# BloopPadMaxx_00.net
KiCad netlist of a schematic drawn in Altium Designer
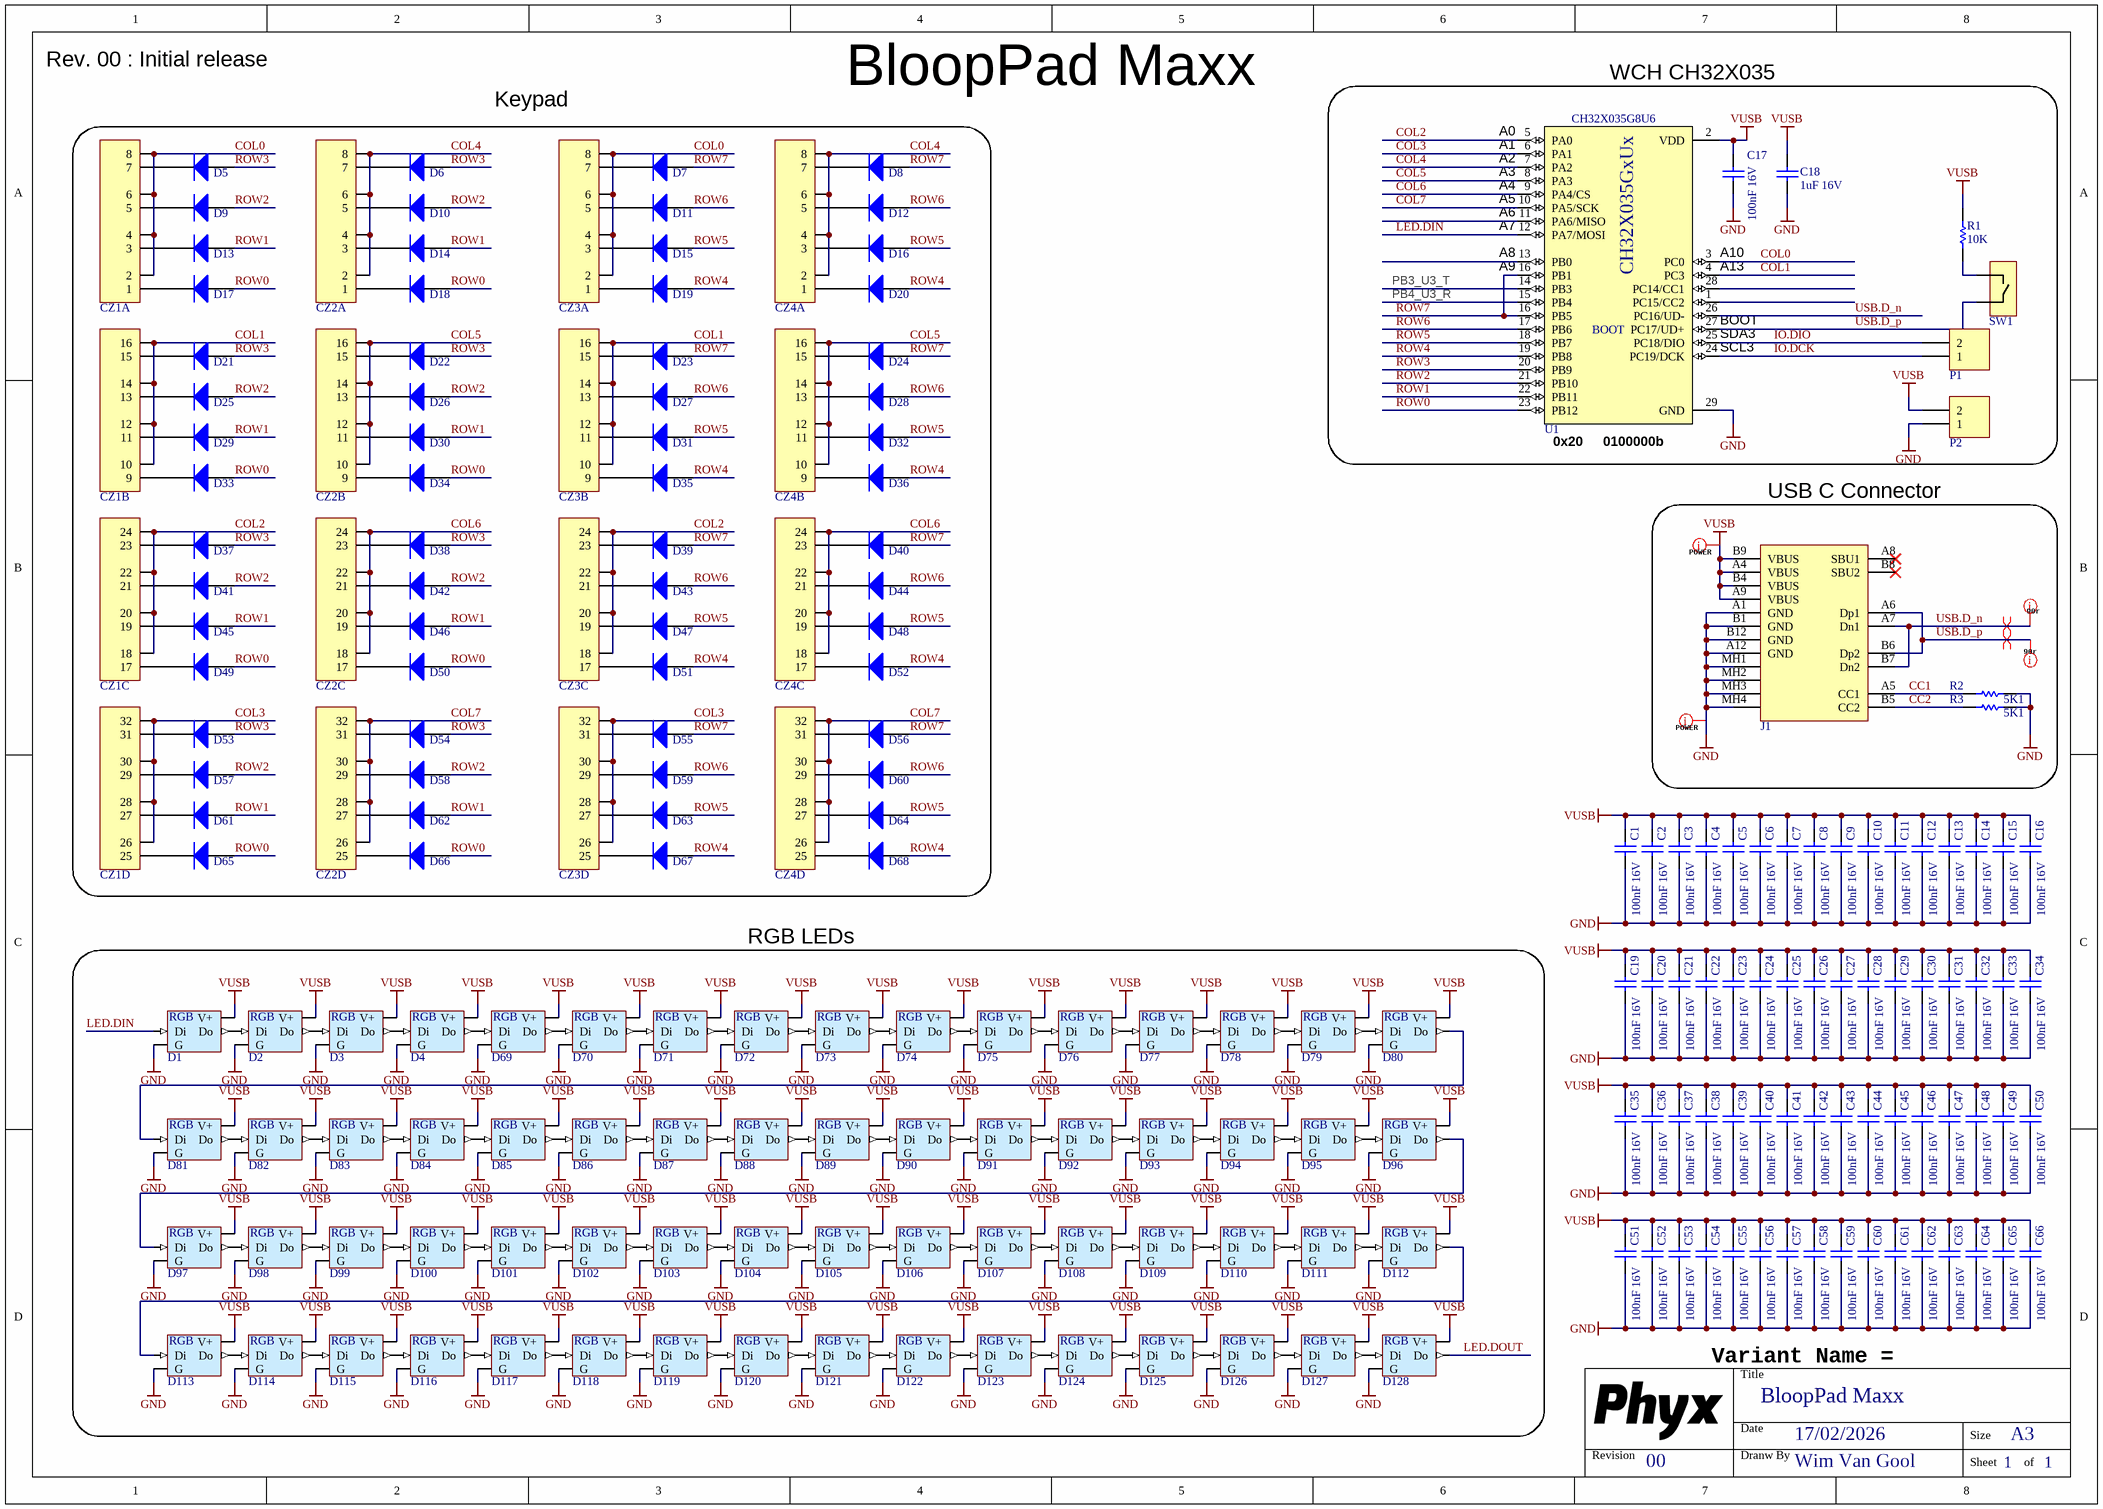
[diagram p0: BloopPadMaxx_00.SchDoc]

(export (version "E")
  (design (tool "Eeschema 10.0.6"))
  (components
    (comp (ref "C1")
      (value "100nF 16V")
      (footprint "C0603_N")
      (description "Capacitor Ceramic")
      (fields (field (name "Comment") "CAP_CERAMIC"))
      (libsource (lib "Phyx_Components") (part "CAP_CERAMIC"))
    )
    (comp (ref "C2")
      (value "100nF 16V")
      (footprint "C0603_N")
      (description "Capacitor Ceramic")
      (fields (field (name "Comment") "CAP_CERAMIC"))
      (libsource (lib "Phyx_Components") (part "CAP_CERAMIC"))
    )
    (comp (ref "C3")
      (value "100nF 16V")
      (footprint "C0603_N")
      (description "Capacitor Ceramic")
      (fields (field (name "Comment") "CAP_CERAMIC"))
      (libsource (lib "Phyx_Components") (part "CAP_CERAMIC"))
    )
    (comp (ref "C4")
      (value "100nF 16V")
      (footprint "C0603_N")
      (description "Capacitor Ceramic")
      (fields (field (name "Comment") "CAP_CERAMIC"))
      (libsource (lib "Phyx_Components") (part "CAP_CERAMIC"))
    )
    (comp (ref "C5")
      (value "100nF 16V")
      (footprint "C0603_N")
      (description "Capacitor Ceramic")
      (fields (field (name "Comment") "CAP_CERAMIC"))
      (libsource (lib "Phyx_Components") (part "CAP_CERAMIC"))
    )
    (comp (ref "C6")
      (value "100nF 16V")
      (footprint "C0603_N")
      (description "Capacitor Ceramic")
      (fields (field (name "Comment") "CAP_CERAMIC"))
      (libsource (lib "Phyx_Components") (part "CAP_CERAMIC"))
    )
    (comp (ref "C7")
      (value "100nF 16V")
      (footprint "C0603_N")
      (description "Capacitor Ceramic")
      (fields (field (name "Comment") "CAP_CERAMIC"))
      (libsource (lib "Phyx_Components") (part "CAP_CERAMIC"))
    )
    (comp (ref "C8")
      (value "100nF 16V")
      (footprint "C0603_N")
      (description "Capacitor Ceramic")
      (fields (field (name "Comment") "CAP_CERAMIC"))
      (libsource (lib "Phyx_Components") (part "CAP_CERAMIC"))
    )
    (comp (ref "C9")
      (value "100nF 16V")
      (footprint "C0603_N")
      (description "Capacitor Ceramic")
      (fields (field (name "Comment") "CAP_CERAMIC"))
      (libsource (lib "Phyx_Components") (part "CAP_CERAMIC"))
    )
    (comp (ref "C10")
      (value "100nF 16V")
      (footprint "C0603_N")
      (description "Capacitor Ceramic")
      (fields (field (name "Comment") "CAP_CERAMIC"))
      (libsource (lib "Phyx_Components") (part "CAP_CERAMIC"))
    )
    (comp (ref "C11")
      (value "100nF 16V")
      (footprint "C0603_N")
      (description "Capacitor Ceramic")
      (fields (field (name "Comment") "CAP_CERAMIC"))
      (libsource (lib "Phyx_Components") (part "CAP_CERAMIC"))
    )
    (comp (ref "C12")
      (value "100nF 16V")
      (footprint "C0603_N")
      (description "Capacitor Ceramic")
      (fields (field (name "Comment") "CAP_CERAMIC"))
      (libsource (lib "Phyx_Components") (part "CAP_CERAMIC"))
    )
    (comp (ref "C13")
      (value "100nF 16V")
      (footprint "C0603_N")
      (description "Capacitor Ceramic")
      (fields (field (name "Comment") "CAP_CERAMIC"))
      (libsource (lib "Phyx_Components") (part "CAP_CERAMIC"))
    )
    (comp (ref "C14")
      (value "100nF 16V")
      (footprint "C0603_N")
      (description "Capacitor Ceramic")
      (fields (field (name "Comment") "CAP_CERAMIC"))
      (libsource (lib "Phyx_Components") (part "CAP_CERAMIC"))
    )
    (comp (ref "C15")
      (value "100nF 16V")
      (footprint "C0603_N")
      (description "Capacitor Ceramic")
      (fields (field (name "Comment") "CAP_CERAMIC"))
      (libsource (lib "Phyx_Components") (part "CAP_CERAMIC"))
    )
    (comp (ref "C16")
      (value "100nF 16V")
      (footprint "C0603_N")
      (description "Capacitor Ceramic")
      (fields (field (name "Comment") "CAP_CERAMIC"))
      (libsource (lib "Phyx_Components") (part "CAP_CERAMIC"))
    )
    (comp (ref "C17")
      (value "100nF 16V")
      (footprint "C0603_N")
      (description "Capacitor Ceramic")
      (libsource (lib "Phyx_Components") (part "CAP_CERAMIC"))
    )
    (comp (ref "C18")
      (value "1uF 16V")
      (footprint "C0603_N")
      (description "Capacitor Ceramic")
      (libsource (lib "Phyx_Components") (part "CAP_CERAMIC"))
    )
    (comp (ref "C19")
      (value "100nF 16V")
      (footprint "C0603_N")
      (description "Capacitor Ceramic")
      (fields (field (name "Comment") "CAP_CERAMIC"))
      (libsource (lib "Phyx_Components") (part "CAP_CERAMIC"))
    )
    (comp (ref "C20")
      (value "100nF 16V")
      (footprint "C0603_N")
      (description "Capacitor Ceramic")
      (fields (field (name "Comment") "CAP_CERAMIC"))
      (libsource (lib "Phyx_Components") (part "CAP_CERAMIC"))
    )
    (comp (ref "C21")
      (value "100nF 16V")
      (footprint "C0603_N")
      (description "Capacitor Ceramic")
      (fields (field (name "Comment") "CAP_CERAMIC"))
      (libsource (lib "Phyx_Components") (part "CAP_CERAMIC"))
    )
    (comp (ref "C22")
      (value "100nF 16V")
      (footprint "C0603_N")
      (description "Capacitor Ceramic")
      (fields (field (name "Comment") "CAP_CERAMIC"))
      (libsource (lib "Phyx_Components") (part "CAP_CERAMIC"))
    )
    (comp (ref "C23")
      (value "100nF 16V")
      (footprint "C0603_N")
      (description "Capacitor Ceramic")
      (fields (field (name "Comment") "CAP_CERAMIC"))
      (libsource (lib "Phyx_Components") (part "CAP_CERAMIC"))
    )
    (comp (ref "C24")
      (value "100nF 16V")
      (footprint "C0603_N")
      (description "Capacitor Ceramic")
      (fields (field (name "Comment") "CAP_CERAMIC"))
      (libsource (lib "Phyx_Components") (part "CAP_CERAMIC"))
    )
    (comp (ref "C25")
      (value "100nF 16V")
      (footprint "C0603_N")
      (description "Capacitor Ceramic")
      (fields (field (name "Comment") "CAP_CERAMIC"))
      (libsource (lib "Phyx_Components") (part "CAP_CERAMIC"))
    )
    (comp (ref "C26")
      (value "100nF 16V")
      (footprint "C0603_N")
      (description "Capacitor Ceramic")
      (fields (field (name "Comment") "CAP_CERAMIC"))
      (libsource (lib "Phyx_Components") (part "CAP_CERAMIC"))
    )
    (comp (ref "C27")
      (value "100nF 16V")
      (footprint "C0603_N")
      (description "Capacitor Ceramic")
      (fields (field (name "Comment") "CAP_CERAMIC"))
      (libsource (lib "Phyx_Components") (part "CAP_CERAMIC"))
    )
    (comp (ref "C28")
      (value "100nF 16V")
      (footprint "C0603_N")
      (description "Capacitor Ceramic")
      (fields (field (name "Comment") "CAP_CERAMIC"))
      (libsource (lib "Phyx_Components") (part "CAP_CERAMIC"))
    )
    (comp (ref "C29")
      (value "100nF 16V")
      (footprint "C0603_N")
      (description "Capacitor Ceramic")
      (fields (field (name "Comment") "CAP_CERAMIC"))
      (libsource (lib "Phyx_Components") (part "CAP_CERAMIC"))
    )
    (comp (ref "C30")
      (value "100nF 16V")
      (footprint "C0603_N")
      (description "Capacitor Ceramic")
      (fields (field (name "Comment") "CAP_CERAMIC"))
      (libsource (lib "Phyx_Components") (part "CAP_CERAMIC"))
    )
    (comp (ref "C31")
      (value "100nF 16V")
      (footprint "C0603_N")
      (description "Capacitor Ceramic")
      (fields (field (name "Comment") "CAP_CERAMIC"))
      (libsource (lib "Phyx_Components") (part "CAP_CERAMIC"))
    )
    (comp (ref "C32")
      (value "100nF 16V")
      (footprint "C0603_N")
      (description "Capacitor Ceramic")
      (fields (field (name "Comment") "CAP_CERAMIC"))
      (libsource (lib "Phyx_Components") (part "CAP_CERAMIC"))
    )
    (comp (ref "C33")
      (value "100nF 16V")
      (footprint "C0603_N")
      (description "Capacitor Ceramic")
      (fields (field (name "Comment") "CAP_CERAMIC"))
      (libsource (lib "Phyx_Components") (part "CAP_CERAMIC"))
    )
    (comp (ref "C34")
      (value "100nF 16V")
      (footprint "C0603_N")
      (description "Capacitor Ceramic")
      (fields (field (name "Comment") "CAP_CERAMIC"))
      (libsource (lib "Phyx_Components") (part "CAP_CERAMIC"))
    )
    (comp (ref "C35")
      (value "100nF 16V")
      (footprint "C0603_N")
      (description "Capacitor Ceramic")
      (fields (field (name "Comment") "CAP_CERAMIC"))
      (libsource (lib "Phyx_Components") (part "CAP_CERAMIC"))
    )
    (comp (ref "C36")
      (value "100nF 16V")
      (footprint "C0603_N")
      (description "Capacitor Ceramic")
      (fields (field (name "Comment") "CAP_CERAMIC"))
      (libsource (lib "Phyx_Components") (part "CAP_CERAMIC"))
    )
    (comp (ref "C37")
      (value "100nF 16V")
      (footprint "C0603_N")
      (description "Capacitor Ceramic")
      (fields (field (name "Comment") "CAP_CERAMIC"))
      (libsource (lib "Phyx_Components") (part "CAP_CERAMIC"))
    )
    (comp (ref "C38")
      (value "100nF 16V")
      (footprint "C0603_N")
      (description "Capacitor Ceramic")
      (fields (field (name "Comment") "CAP_CERAMIC"))
      (libsource (lib "Phyx_Components") (part "CAP_CERAMIC"))
    )
    (comp (ref "C39")
      (value "100nF 16V")
      (footprint "C0603_N")
      (description "Capacitor Ceramic")
      (fields (field (name "Comment") "CAP_CERAMIC"))
      (libsource (lib "Phyx_Components") (part "CAP_CERAMIC"))
    )
    (comp (ref "C40")
      (value "100nF 16V")
      (footprint "C0603_N")
      (description "Capacitor Ceramic")
      (fields (field (name "Comment") "CAP_CERAMIC"))
      (libsource (lib "Phyx_Components") (part "CAP_CERAMIC"))
    )
    (comp (ref "C41")
      (value "100nF 16V")
      (footprint "C0603_N")
      (description "Capacitor Ceramic")
      (fields (field (name "Comment") "CAP_CERAMIC"))
      (libsource (lib "Phyx_Components") (part "CAP_CERAMIC"))
    )
    (comp (ref "C42")
      (value "100nF 16V")
      (footprint "C0603_N")
      (description "Capacitor Ceramic")
      (fields (field (name "Comment") "CAP_CERAMIC"))
      (libsource (lib "Phyx_Components") (part "CAP_CERAMIC"))
    )
    (comp (ref "C43")
      (value "100nF 16V")
      (footprint "C0603_N")
      (description "Capacitor Ceramic")
      (fields (field (name "Comment") "CAP_CERAMIC"))
      (libsource (lib "Phyx_Components") (part "CAP_CERAMIC"))
    )
    (comp (ref "C44")
      (value "100nF 16V")
      (footprint "C0603_N")
      (description "Capacitor Ceramic")
      (fields (field (name "Comment") "CAP_CERAMIC"))
      (libsource (lib "Phyx_Components") (part "CAP_CERAMIC"))
    )
    (comp (ref "C45")
      (value "100nF 16V")
      (footprint "C0603_N")
      (description "Capacitor Ceramic")
      (fields (field (name "Comment") "CAP_CERAMIC"))
      (libsource (lib "Phyx_Components") (part "CAP_CERAMIC"))
    )
    (comp (ref "C46")
      (value "100nF 16V")
      (footprint "C0603_N")
      (description "Capacitor Ceramic")
      (fields (field (name "Comment") "CAP_CERAMIC"))
      (libsource (lib "Phyx_Components") (part "CAP_CERAMIC"))
    )
    (comp (ref "C47")
      (value "100nF 16V")
      (footprint "C0603_N")
      (description "Capacitor Ceramic")
      (fields (field (name "Comment") "CAP_CERAMIC"))
      (libsource (lib "Phyx_Components") (part "CAP_CERAMIC"))
    )
    (comp (ref "C48")
      (value "100nF 16V")
      (footprint "C0603_N")
      (description "Capacitor Ceramic")
      (fields (field (name "Comment") "CAP_CERAMIC"))
      (libsource (lib "Phyx_Components") (part "CAP_CERAMIC"))
    )
    (comp (ref "C49")
      (value "100nF 16V")
      (footprint "C0603_N")
      (description "Capacitor Ceramic")
      (fields (field (name "Comment") "CAP_CERAMIC"))
      (libsource (lib "Phyx_Components") (part "CAP_CERAMIC"))
    )
    (comp (ref "C50")
      (value "100nF 16V")
      (footprint "C0603_N")
      (description "Capacitor Ceramic")
      (fields (field (name "Comment") "CAP_CERAMIC"))
      (libsource (lib "Phyx_Components") (part "CAP_CERAMIC"))
    )
    (comp (ref "C51")
      (value "100nF 16V")
      (footprint "C0603_N")
      (description "Capacitor Ceramic")
      (fields (field (name "Comment") "CAP_CERAMIC"))
      (libsource (lib "Phyx_Components") (part "CAP_CERAMIC"))
    )
    (comp (ref "C52")
      (value "100nF 16V")
      (footprint "C0603_N")
      (description "Capacitor Ceramic")
      (fields (field (name "Comment") "CAP_CERAMIC"))
      (libsource (lib "Phyx_Components") (part "CAP_CERAMIC"))
    )
    (comp (ref "C53")
      (value "100nF 16V")
      (footprint "C0603_N")
      (description "Capacitor Ceramic")
      (fields (field (name "Comment") "CAP_CERAMIC"))
      (libsource (lib "Phyx_Components") (part "CAP_CERAMIC"))
    )
    (comp (ref "C54")
      (value "100nF 16V")
      (footprint "C0603_N")
      (description "Capacitor Ceramic")
      (fields (field (name "Comment") "CAP_CERAMIC"))
      (libsource (lib "Phyx_Components") (part "CAP_CERAMIC"))
    )
    (comp (ref "C55")
      (value "100nF 16V")
      (footprint "C0603_N")
      (description "Capacitor Ceramic")
      (fields (field (name "Comment") "CAP_CERAMIC"))
      (libsource (lib "Phyx_Components") (part "CAP_CERAMIC"))
    )
    (comp (ref "C56")
      (value "100nF 16V")
      (footprint "C0603_N")
      (description "Capacitor Ceramic")
      (fields (field (name "Comment") "CAP_CERAMIC"))
      (libsource (lib "Phyx_Components") (part "CAP_CERAMIC"))
    )
    (comp (ref "C57")
      (value "100nF 16V")
      (footprint "C0603_N")
      (description "Capacitor Ceramic")
      (fields (field (name "Comment") "CAP_CERAMIC"))
      (libsource (lib "Phyx_Components") (part "CAP_CERAMIC"))
    )
    (comp (ref "C58")
      (value "100nF 16V")
      (footprint "C0603_N")
      (description "Capacitor Ceramic")
      (fields (field (name "Comment") "CAP_CERAMIC"))
      (libsource (lib "Phyx_Components") (part "CAP_CERAMIC"))
    )
    (comp (ref "C59")
      (value "100nF 16V")
      (footprint "C0603_N")
      (description "Capacitor Ceramic")
      (fields (field (name "Comment") "CAP_CERAMIC"))
      (libsource (lib "Phyx_Components") (part "CAP_CERAMIC"))
    )
    (comp (ref "C60")
      (value "100nF 16V")
      (footprint "C0603_N")
      (description "Capacitor Ceramic")
      (fields (field (name "Comment") "CAP_CERAMIC"))
      (libsource (lib "Phyx_Components") (part "CAP_CERAMIC"))
    )
    (comp (ref "C61")
      (value "100nF 16V")
      (footprint "C0603_N")
      (description "Capacitor Ceramic")
      (fields (field (name "Comment") "CAP_CERAMIC"))
      (libsource (lib "Phyx_Components") (part "CAP_CERAMIC"))
    )
    (comp (ref "C62")
      (value "100nF 16V")
      (footprint "C0603_N")
      (description "Capacitor Ceramic")
      (fields (field (name "Comment") "CAP_CERAMIC"))
      (libsource (lib "Phyx_Components") (part "CAP_CERAMIC"))
    )
    (comp (ref "C63")
      (value "100nF 16V")
      (footprint "C0603_N")
      (description "Capacitor Ceramic")
      (fields (field (name "Comment") "CAP_CERAMIC"))
      (libsource (lib "Phyx_Components") (part "CAP_CERAMIC"))
    )
    (comp (ref "C64")
      (value "100nF 16V")
      (footprint "C0603_N")
      (description "Capacitor Ceramic")
      (fields (field (name "Comment") "CAP_CERAMIC"))
      (libsource (lib "Phyx_Components") (part "CAP_CERAMIC"))
    )
    (comp (ref "C65")
      (value "100nF 16V")
      (footprint "C0603_N")
      (description "Capacitor Ceramic")
      (fields (field (name "Comment") "CAP_CERAMIC"))
      (libsource (lib "Phyx_Components") (part "CAP_CERAMIC"))
    )
    (comp (ref "C66")
      (value "100nF 16V")
      (footprint "C0603_N")
      (description "Capacitor Ceramic")
      (fields (field (name "Comment") "CAP_CERAMIC"))
      (libsource (lib "Phyx_Components") (part "CAP_CERAMIC"))
    )
    (comp (ref "CZ1")
      (value "Campzone 2020 4x4 silicone keypad")
      (footprint "CZ20_4x4")
      (libsource (lib "Phyx_Components") (part "CZ20_4x4"))
    )
    (comp (ref "CZ2")
      (value "Campzone 2020 4x4 silicone keypad")
      (footprint "CZ20_4x4")
      (libsource (lib "Phyx_Components") (part "CZ20_4x4"))
    )
    (comp (ref "CZ3")
      (value "Campzone 2020 4x4 silicone keypad")
      (footprint "CZ20_4x4")
      (libsource (lib "Phyx_Components") (part "CZ20_4x4"))
    )
    (comp (ref "CZ4")
      (value "Campzone 2020 4x4 silicone keypad")
      (footprint "CZ20_4x4")
      (libsource (lib "Phyx_Components") (part "CZ20_4x4"))
    )
    (comp (ref "D1")
      (value "WS2812 based digital RGB LED 2022 package")
      (footprint "LED_2022_WS2812B")
      (description "=Description")
      (libsource (lib "Phyx_Components") (part "LED_RGB_WS2812B_2022"))
    )
    (comp (ref "D2")
      (value "WS2812 based digital RGB LED 2022 package")
      (footprint "LED_2022_WS2812B")
      (description "=Description")
      (libsource (lib "Phyx_Components") (part "LED_RGB_WS2812B_2022"))
    )
    (comp (ref "D3")
      (value "WS2812 based digital RGB LED 2022 package")
      (footprint "LED_2022_WS2812B")
      (description "=Description")
      (libsource (lib "Phyx_Components") (part "LED_RGB_WS2812B_2022"))
    )
    (comp (ref "D4")
      (value "WS2812 based digital RGB LED 2022 package")
      (footprint "LED_2022_WS2812B")
      (description "=Description")
      (libsource (lib "Phyx_Components") (part "LED_RGB_WS2812B_2022"))
    )
    (comp (ref "D5")
      (value "1N4148W 75V 200mA 1.25Vf@150mA")
      (footprint "SOD-323_AC")
      (description "Default Diode")
      (libsource (lib "Phyx_Components") (part "DIODE_AC"))
    )
    (comp (ref "D6")
      (value "1N4148W 75V 200mA 1.25Vf@150mA")
      (footprint "SOD-323_AC")
      (description "Default Diode")
      (libsource (lib "Phyx_Components") (part "DIODE_AC"))
    )
    (comp (ref "D7")
      (value "1N4148W 75V 200mA 1.25Vf@150mA")
      (footprint "SOD-323_AC")
      (description "Default Diode")
      (libsource (lib "Phyx_Components") (part "DIODE_AC"))
    )
    (comp (ref "D8")
      (value "1N4148W 75V 200mA 1.25Vf@150mA")
      (footprint "SOD-323_AC")
      (description "Default Diode")
      (libsource (lib "Phyx_Components") (part "DIODE_AC"))
    )
    (comp (ref "D9")
      (value "1N4148W 75V 200mA 1.25Vf@150mA")
      (footprint "SOD-323_AC")
      (description "Default Diode")
      (libsource (lib "Phyx_Components") (part "DIODE_AC"))
    )
    (comp (ref "D10")
      (value "1N4148W 75V 200mA 1.25Vf@150mA")
      (footprint "SOD-323_AC")
      (description "Default Diode")
      (libsource (lib "Phyx_Components") (part "DIODE_AC"))
    )
    (comp (ref "D11")
      (value "1N4148W 75V 200mA 1.25Vf@150mA")
      (footprint "SOD-323_AC")
      (description "Default Diode")
      (libsource (lib "Phyx_Components") (part "DIODE_AC"))
    )
    (comp (ref "D12")
      (value "1N4148W 75V 200mA 1.25Vf@150mA")
      (footprint "SOD-323_AC")
      (description "Default Diode")
      (libsource (lib "Phyx_Components") (part "DIODE_AC"))
    )
    (comp (ref "D13")
      (value "1N4148W 75V 200mA 1.25Vf@150mA")
      (footprint "SOD-323_AC")
      (description "Default Diode")
      (libsource (lib "Phyx_Components") (part "DIODE_AC"))
    )
    (comp (ref "D14")
      (value "1N4148W 75V 200mA 1.25Vf@150mA")
      (footprint "SOD-323_AC")
      (description "Default Diode")
      (libsource (lib "Phyx_Components") (part "DIODE_AC"))
    )
    (comp (ref "D15")
      (value "1N4148W 75V 200mA 1.25Vf@150mA")
      (footprint "SOD-323_AC")
      (description "Default Diode")
      (libsource (lib "Phyx_Components") (part "DIODE_AC"))
    )
    (comp (ref "D16")
      (value "1N4148W 75V 200mA 1.25Vf@150mA")
      (footprint "SOD-323_AC")
      (description "Default Diode")
      (libsource (lib "Phyx_Components") (part "DIODE_AC"))
    )
    (comp (ref "D17")
      (value "1N4148W 75V 200mA 1.25Vf@150mA")
      (footprint "SOD-323_AC")
      (description "Default Diode")
      (libsource (lib "Phyx_Components") (part "DIODE_AC"))
    )
    (comp (ref "D18")
      (value "1N4148W 75V 200mA 1.25Vf@150mA")
      (footprint "SOD-323_AC")
      (description "Default Diode")
      (libsource (lib "Phyx_Components") (part "DIODE_AC"))
    )
    (comp (ref "D19")
      (value "1N4148W 75V 200mA 1.25Vf@150mA")
      (footprint "SOD-323_AC")
      (description "Default Diode")
      (libsource (lib "Phyx_Components") (part "DIODE_AC"))
    )
    (comp (ref "D20")
      (value "1N4148W 75V 200mA 1.25Vf@150mA")
      (footprint "SOD-323_AC")
      (description "Default Diode")
      (libsource (lib "Phyx_Components") (part "DIODE_AC"))
    )
    (comp (ref "D21")
      (value "1N4148W 75V 200mA 1.25Vf@150mA")
      (footprint "SOD-323_AC")
      (description "Default Diode")
      (libsource (lib "Phyx_Components") (part "DIODE_AC"))
    )
    (comp (ref "D22")
      (value "1N4148W 75V 200mA 1.25Vf@150mA")
      (footprint "SOD-323_AC")
      (description "Default Diode")
      (libsource (lib "Phyx_Components") (part "DIODE_AC"))
    )
    (comp (ref "D23")
      (value "1N4148W 75V 200mA 1.25Vf@150mA")
      (footprint "SOD-323_AC")
      (description "Default Diode")
      (libsource (lib "Phyx_Components") (part "DIODE_AC"))
    )
    (comp (ref "D24")
      (value "1N4148W 75V 200mA 1.25Vf@150mA")
      (footprint "SOD-323_AC")
      (description "Default Diode")
      (libsource (lib "Phyx_Components") (part "DIODE_AC"))
    )
    (comp (ref "D25")
      (value "1N4148W 75V 200mA 1.25Vf@150mA")
      (footprint "SOD-323_AC")
      (description "Default Diode")
      (libsource (lib "Phyx_Components") (part "DIODE_AC"))
    )
    (comp (ref "D26")
      (value "1N4148W 75V 200mA 1.25Vf@150mA")
      (footprint "SOD-323_AC")
      (description "Default Diode")
      (libsource (lib "Phyx_Components") (part "DIODE_AC"))
    )
    (comp (ref "D27")
      (value "1N4148W 75V 200mA 1.25Vf@150mA")
      (footprint "SOD-323_AC")
      (description "Default Diode")
      (libsource (lib "Phyx_Components") (part "DIODE_AC"))
    )
    (comp (ref "D28")
      (value "1N4148W 75V 200mA 1.25Vf@150mA")
      (footprint "SOD-323_AC")
      (description "Default Diode")
      (libsource (lib "Phyx_Components") (part "DIODE_AC"))
    )
    (comp (ref "D29")
      (value "1N4148W 75V 200mA 1.25Vf@150mA")
      (footprint "SOD-323_AC")
      (description "Default Diode")
      (libsource (lib "Phyx_Components") (part "DIODE_AC"))
    )
    (comp (ref "D30")
      (value "1N4148W 75V 200mA 1.25Vf@150mA")
      (footprint "SOD-323_AC")
      (description "Default Diode")
      (libsource (lib "Phyx_Components") (part "DIODE_AC"))
    )
    (comp (ref "D31")
      (value "1N4148W 75V 200mA 1.25Vf@150mA")
      (footprint "SOD-323_AC")
      (description "Default Diode")
      (libsource (lib "Phyx_Components") (part "DIODE_AC"))
    )
    (comp (ref "D32")
      (value "1N4148W 75V 200mA 1.25Vf@150mA")
      (footprint "SOD-323_AC")
      (description "Default Diode")
      (libsource (lib "Phyx_Components") (part "DIODE_AC"))
    )
    (comp (ref "D33")
      (value "1N4148W 75V 200mA 1.25Vf@150mA")
      (footprint "SOD-323_AC")
      (description "Default Diode")
      (libsource (lib "Phyx_Components") (part "DIODE_AC"))
    )
    (comp (ref "D34")
      (value "1N4148W 75V 200mA 1.25Vf@150mA")
      (footprint "SOD-323_AC")
      (description "Default Diode")
      (libsource (lib "Phyx_Components") (part "DIODE_AC"))
    )
    (comp (ref "D35")
      (value "1N4148W 75V 200mA 1.25Vf@150mA")
      (footprint "SOD-323_AC")
      (description "Default Diode")
      (libsource (lib "Phyx_Components") (part "DIODE_AC"))
    )
    (comp (ref "D36")
      (value "1N4148W 75V 200mA 1.25Vf@150mA")
      (footprint "SOD-323_AC")
      (description "Default Diode")
      (libsource (lib "Phyx_Components") (part "DIODE_AC"))
    )
    (comp (ref "D37")
      (value "1N4148W 75V 200mA 1.25Vf@150mA")
      (footprint "SOD-323_AC")
      (description "Default Diode")
      (libsource (lib "Phyx_Components") (part "DIODE_AC"))
    )
    (comp (ref "D38")
      (value "1N4148W 75V 200mA 1.25Vf@150mA")
      (footprint "SOD-323_AC")
      (description "Default Diode")
      (libsource (lib "Phyx_Components") (part "DIODE_AC"))
    )
    (comp (ref "D39")
      (value "1N4148W 75V 200mA 1.25Vf@150mA")
      (footprint "SOD-323_AC")
      (description "Default Diode")
      (libsource (lib "Phyx_Components") (part "DIODE_AC"))
    )
    (comp (ref "D40")
      (value "1N4148W 75V 200mA 1.25Vf@150mA")
      (footprint "SOD-323_AC")
      (description "Default Diode")
      (libsource (lib "Phyx_Components") (part "DIODE_AC"))
    )
    (comp (ref "D41")
      (value "1N4148W 75V 200mA 1.25Vf@150mA")
      (footprint "SOD-323_AC")
      (description "Default Diode")
      (libsource (lib "Phyx_Components") (part "DIODE_AC"))
    )
    (comp (ref "D42")
      (value "1N4148W 75V 200mA 1.25Vf@150mA")
      (footprint "SOD-323_AC")
      (description "Default Diode")
      (libsource (lib "Phyx_Components") (part "DIODE_AC"))
    )
    (comp (ref "D43")
      (value "1N4148W 75V 200mA 1.25Vf@150mA")
      (footprint "SOD-323_AC")
      (description "Default Diode")
      (libsource (lib "Phyx_Components") (part "DIODE_AC"))
    )
    (comp (ref "D44")
      (value "1N4148W 75V 200mA 1.25Vf@150mA")
      (footprint "SOD-323_AC")
      (description "Default Diode")
      (libsource (lib "Phyx_Components") (part "DIODE_AC"))
    )
    (comp (ref "D45")
      (value "1N4148W 75V 200mA 1.25Vf@150mA")
      (footprint "SOD-323_AC")
      (description "Default Diode")
      (libsource (lib "Phyx_Components") (part "DIODE_AC"))
    )
    (comp (ref "D46")
      (value "1N4148W 75V 200mA 1.25Vf@150mA")
      (footprint "SOD-323_AC")
      (description "Default Diode")
      (libsource (lib "Phyx_Components") (part "DIODE_AC"))
    )
    (comp (ref "D47")
      (value "1N4148W 75V 200mA 1.25Vf@150mA")
      (footprint "SOD-323_AC")
      (description "Default Diode")
      (libsource (lib "Phyx_Components") (part "DIODE_AC"))
    )
    (comp (ref "D48")
      (value "1N4148W 75V 200mA 1.25Vf@150mA")
      (footprint "SOD-323_AC")
      (description "Default Diode")
      (libsource (lib "Phyx_Components") (part "DIODE_AC"))
    )
    (comp (ref "D49")
      (value "1N4148W 75V 200mA 1.25Vf@150mA")
      (footprint "SOD-323_AC")
      (description "Default Diode")
      (libsource (lib "Phyx_Components") (part "DIODE_AC"))
    )
    (comp (ref "D50")
      (value "1N4148W 75V 200mA 1.25Vf@150mA")
      (footprint "SOD-323_AC")
      (description "Default Diode")
      (libsource (lib "Phyx_Components") (part "DIODE_AC"))
    )
    (comp (ref "D51")
      (value "1N4148W 75V 200mA 1.25Vf@150mA")
      (footprint "SOD-323_AC")
      (description "Default Diode")
      (libsource (lib "Phyx_Components") (part "DIODE_AC"))
    )
    (comp (ref "D52")
      (value "1N4148W 75V 200mA 1.25Vf@150mA")
      (footprint "SOD-323_AC")
      (description "Default Diode")
      (libsource (lib "Phyx_Components") (part "DIODE_AC"))
    )
    (comp (ref "D53")
      (value "1N4148W 75V 200mA 1.25Vf@150mA")
      (footprint "SOD-323_AC")
      (description "Default Diode")
      (libsource (lib "Phyx_Components") (part "DIODE_AC"))
    )
    (comp (ref "D54")
      (value "1N4148W 75V 200mA 1.25Vf@150mA")
      (footprint "SOD-323_AC")
      (description "Default Diode")
      (libsource (lib "Phyx_Components") (part "DIODE_AC"))
    )
    (comp (ref "D55")
      (value "1N4148W 75V 200mA 1.25Vf@150mA")
      (footprint "SOD-323_AC")
      (description "Default Diode")
      (libsource (lib "Phyx_Components") (part "DIODE_AC"))
    )
    (comp (ref "D56")
      (value "1N4148W 75V 200mA 1.25Vf@150mA")
      (footprint "SOD-323_AC")
      (description "Default Diode")
      (libsource (lib "Phyx_Components") (part "DIODE_AC"))
    )
    (comp (ref "D57")
      (value "1N4148W 75V 200mA 1.25Vf@150mA")
      (footprint "SOD-323_AC")
      (description "Default Diode")
      (libsource (lib "Phyx_Components") (part "DIODE_AC"))
    )
    (comp (ref "D58")
      (value "1N4148W 75V 200mA 1.25Vf@150mA")
      (footprint "SOD-323_AC")
      (description "Default Diode")
      (libsource (lib "Phyx_Components") (part "DIODE_AC"))
    )
    (comp (ref "D59")
      (value "1N4148W 75V 200mA 1.25Vf@150mA")
      (footprint "SOD-323_AC")
      (description "Default Diode")
      (libsource (lib "Phyx_Components") (part "DIODE_AC"))
    )
    (comp (ref "D60")
      (value "1N4148W 75V 200mA 1.25Vf@150mA")
      (footprint "SOD-323_AC")
      (description "Default Diode")
      (libsource (lib "Phyx_Components") (part "DIODE_AC"))
    )
    (comp (ref "D61")
      (value "1N4148W 75V 200mA 1.25Vf@150mA")
      (footprint "SOD-323_AC")
      (description "Default Diode")
      (libsource (lib "Phyx_Components") (part "DIODE_AC"))
    )
    (comp (ref "D62")
      (value "1N4148W 75V 200mA 1.25Vf@150mA")
      (footprint "SOD-323_AC")
      (description "Default Diode")
      (libsource (lib "Phyx_Components") (part "DIODE_AC"))
    )
    (comp (ref "D63")
      (value "1N4148W 75V 200mA 1.25Vf@150mA")
      (footprint "SOD-323_AC")
      (description "Default Diode")
      (libsource (lib "Phyx_Components") (part "DIODE_AC"))
    )
    (comp (ref "D64")
      (value "1N4148W 75V 200mA 1.25Vf@150mA")
      (footprint "SOD-323_AC")
      (description "Default Diode")
      (libsource (lib "Phyx_Components") (part "DIODE_AC"))
    )
    (comp (ref "D65")
      (value "1N4148W 75V 200mA 1.25Vf@150mA")
      (footprint "SOD-323_AC")
      (description "Default Diode")
      (libsource (lib "Phyx_Components") (part "DIODE_AC"))
    )
    (comp (ref "D66")
      (value "1N4148W 75V 200mA 1.25Vf@150mA")
      (footprint "SOD-323_AC")
      (description "Default Diode")
      (libsource (lib "Phyx_Components") (part "DIODE_AC"))
    )
    (comp (ref "D67")
      (value "1N4148W 75V 200mA 1.25Vf@150mA")
      (footprint "SOD-323_AC")
      (description "Default Diode")
      (libsource (lib "Phyx_Components") (part "DIODE_AC"))
    )
    (comp (ref "D68")
      (value "1N4148W 75V 200mA 1.25Vf@150mA")
      (footprint "SOD-323_AC")
      (description "Default Diode")
      (libsource (lib "Phyx_Components") (part "DIODE_AC"))
    )
    (comp (ref "D69")
      (value "WS2812 based digital RGB LED 2022 package")
      (footprint "LED_2022_WS2812B")
      (description "=Description")
      (libsource (lib "Phyx_Components") (part "LED_RGB_WS2812B_2022"))
    )
    (comp (ref "D70")
      (value "WS2812 based digital RGB LED 2022 package")
      (footprint "LED_2022_WS2812B")
      (description "=Description")
      (libsource (lib "Phyx_Components") (part "LED_RGB_WS2812B_2022"))
    )
    (comp (ref "D71")
      (value "WS2812 based digital RGB LED 2022 package")
      (footprint "LED_2022_WS2812B")
      (description "=Description")
      (libsource (lib "Phyx_Components") (part "LED_RGB_WS2812B_2022"))
    )
    (comp (ref "D72")
      (value "WS2812 based digital RGB LED 2022 package")
      (footprint "LED_2022_WS2812B")
      (description "=Description")
      (libsource (lib "Phyx_Components") (part "LED_RGB_WS2812B_2022"))
    )
    (comp (ref "D73")
      (value "WS2812 based digital RGB LED 2022 package")
      (footprint "LED_2022_WS2812B")
      (description "=Description")
      (libsource (lib "Phyx_Components") (part "LED_RGB_WS2812B_2022"))
    )
    (comp (ref "D74")
      (value "WS2812 based digital RGB LED 2022 package")
      (footprint "LED_2022_WS2812B")
      (description "=Description")
      (libsource (lib "Phyx_Components") (part "LED_RGB_WS2812B_2022"))
    )
    (comp (ref "D75")
      (value "WS2812 based digital RGB LED 2022 package")
      (footprint "LED_2022_WS2812B")
      (description "=Description")
      (libsource (lib "Phyx_Components") (part "LED_RGB_WS2812B_2022"))
    )
    (comp (ref "D76")
      (value "WS2812 based digital RGB LED 2022 package")
      (footprint "LED_2022_WS2812B")
      (description "=Description")
      (libsource (lib "Phyx_Components") (part "LED_RGB_WS2812B_2022"))
    )
    (comp (ref "D77")
      (value "WS2812 based digital RGB LED 2022 package")
      (footprint "LED_2022_WS2812B")
      (description "=Description")
      (libsource (lib "Phyx_Components") (part "LED_RGB_WS2812B_2022"))
    )
    (comp (ref "D78")
      (value "WS2812 based digital RGB LED 2022 package")
      (footprint "LED_2022_WS2812B")
      (description "=Description")
      (libsource (lib "Phyx_Components") (part "LED_RGB_WS2812B_2022"))
    )
    (comp (ref "D79")
      (value "WS2812 based digital RGB LED 2022 package")
      (footprint "LED_2022_WS2812B")
      (description "=Description")
      (libsource (lib "Phyx_Components") (part "LED_RGB_WS2812B_2022"))
    )
    (comp (ref "D80")
      (value "WS2812 based digital RGB LED 2022 package")
      (footprint "LED_2022_WS2812B")
      (description "=Description")
      (libsource (lib "Phyx_Components") (part "LED_RGB_WS2812B_2022"))
    )
    (comp (ref "D81")
      (value "WS2812 based digital RGB LED 2022 package")
      (footprint "LED_2022_WS2812B")
      (description "=Description")
      (libsource (lib "Phyx_Components") (part "LED_RGB_WS2812B_2022"))
    )
    (comp (ref "D82")
      (value "WS2812 based digital RGB LED 2022 package")
      (footprint "LED_2022_WS2812B")
      (description "=Description")
      (libsource (lib "Phyx_Components") (part "LED_RGB_WS2812B_2022"))
    )
    (comp (ref "D83")
      (value "WS2812 based digital RGB LED 2022 package")
      (footprint "LED_2022_WS2812B")
      (description "=Description")
      (libsource (lib "Phyx_Components") (part "LED_RGB_WS2812B_2022"))
    )
    (comp (ref "D84")
      (value "WS2812 based digital RGB LED 2022 package")
      (footprint "LED_2022_WS2812B")
      (description "=Description")
      (libsource (lib "Phyx_Components") (part "LED_RGB_WS2812B_2022"))
    )
    (comp (ref "D85")
      (value "WS2812 based digital RGB LED 2022 package")
      (footprint "LED_2022_WS2812B")
      (description "=Description")
      (libsource (lib "Phyx_Components") (part "LED_RGB_WS2812B_2022"))
    )
    (comp (ref "D86")
      (value "WS2812 based digital RGB LED 2022 package")
      (footprint "LED_2022_WS2812B")
      (description "=Description")
      (libsource (lib "Phyx_Components") (part "LED_RGB_WS2812B_2022"))
    )
    (comp (ref "D87")
      (value "WS2812 based digital RGB LED 2022 package")
      (footprint "LED_2022_WS2812B")
      (description "=Description")
      (libsource (lib "Phyx_Components") (part "LED_RGB_WS2812B_2022"))
    )
    (comp (ref "D88")
      (value "WS2812 based digital RGB LED 2022 package")
      (footprint "LED_2022_WS2812B")
      (description "=Description")
      (libsource (lib "Phyx_Components") (part "LED_RGB_WS2812B_2022"))
    )
    (comp (ref "D89")
      (value "WS2812 based digital RGB LED 2022 package")
      (footprint "LED_2022_WS2812B")
      (description "=Description")
      (libsource (lib "Phyx_Components") (part "LED_RGB_WS2812B_2022"))
    )
    (comp (ref "D90")
      (value "WS2812 based digital RGB LED 2022 package")
      (footprint "LED_2022_WS2812B")
      (description "=Description")
      (libsource (lib "Phyx_Components") (part "LED_RGB_WS2812B_2022"))
    )
    (comp (ref "D91")
      (value "WS2812 based digital RGB LED 2022 package")
      (footprint "LED_2022_WS2812B")
      (description "=Description")
      (libsource (lib "Phyx_Components") (part "LED_RGB_WS2812B_2022"))
    )
    (comp (ref "D92")
      (value "WS2812 based digital RGB LED 2022 package")
      (footprint "LED_2022_WS2812B")
      (description "=Description")
      (libsource (lib "Phyx_Components") (part "LED_RGB_WS2812B_2022"))
    )
    (comp (ref "D93")
      (value "WS2812 based digital RGB LED 2022 package")
      (footprint "LED_2022_WS2812B")
      (description "=Description")
      (libsource (lib "Phyx_Components") (part "LED_RGB_WS2812B_2022"))
    )
    (comp (ref "D94")
      (value "WS2812 based digital RGB LED 2022 package")
      (footprint "LED_2022_WS2812B")
      (description "=Description")
      (libsource (lib "Phyx_Components") (part "LED_RGB_WS2812B_2022"))
    )
    (comp (ref "D95")
      (value "WS2812 based digital RGB LED 2022 package")
      (footprint "LED_2022_WS2812B")
      (description "=Description")
      (libsource (lib "Phyx_Components") (part "LED_RGB_WS2812B_2022"))
    )
    (comp (ref "D96")
      (value "WS2812 based digital RGB LED 2022 package")
      (footprint "LED_2022_WS2812B")
      (description "=Description")
      (libsource (lib "Phyx_Components") (part "LED_RGB_WS2812B_2022"))
    )
    (comp (ref "D97")
      (value "WS2812 based digital RGB LED 2022 package")
      (footprint "LED_2022_WS2812B")
      (description "=Description")
      (libsource (lib "Phyx_Components") (part "LED_RGB_WS2812B_2022"))
    )
    (comp (ref "D98")
      (value "WS2812 based digital RGB LED 2022 package")
      (footprint "LED_2022_WS2812B")
      (description "=Description")
      (libsource (lib "Phyx_Components") (part "LED_RGB_WS2812B_2022"))
    )
    (comp (ref "D99")
      (value "WS2812 based digital RGB LED 2022 package")
      (footprint "LED_2022_WS2812B")
      (description "=Description")
      (libsource (lib "Phyx_Components") (part "LED_RGB_WS2812B_2022"))
    )
    (comp (ref "D100")
      (value "WS2812 based digital RGB LED 2022 package")
      (footprint "LED_2022_WS2812B")
      (description "=Description")
      (libsource (lib "Phyx_Components") (part "LED_RGB_WS2812B_2022"))
    )
    (comp (ref "D101")
      (value "WS2812 based digital RGB LED 2022 package")
      (footprint "LED_2022_WS2812B")
      (description "=Description")
      (libsource (lib "Phyx_Components") (part "LED_RGB_WS2812B_2022"))
    )
    (comp (ref "D102")
      (value "WS2812 based digital RGB LED 2022 package")
      (footprint "LED_2022_WS2812B")
      (description "=Description")
      (libsource (lib "Phyx_Components") (part "LED_RGB_WS2812B_2022"))
    )
    (comp (ref "D103")
      (value "WS2812 based digital RGB LED 2022 package")
      (footprint "LED_2022_WS2812B")
      (description "=Description")
      (libsource (lib "Phyx_Components") (part "LED_RGB_WS2812B_2022"))
    )
    (comp (ref "D104")
      (value "WS2812 based digital RGB LED 2022 package")
      (footprint "LED_2022_WS2812B")
      (description "=Description")
      (libsource (lib "Phyx_Components") (part "LED_RGB_WS2812B_2022"))
    )
    (comp (ref "D105")
      (value "WS2812 based digital RGB LED 2022 package")
      (footprint "LED_2022_WS2812B")
      (description "=Description")
      (libsource (lib "Phyx_Components") (part "LED_RGB_WS2812B_2022"))
    )
    (comp (ref "D106")
      (value "WS2812 based digital RGB LED 2022 package")
      (footprint "LED_2022_WS2812B")
      (description "=Description")
      (libsource (lib "Phyx_Components") (part "LED_RGB_WS2812B_2022"))
    )
    (comp (ref "D107")
      (value "WS2812 based digital RGB LED 2022 package")
      (footprint "LED_2022_WS2812B")
      (description "=Description")
      (libsource (lib "Phyx_Components") (part "LED_RGB_WS2812B_2022"))
    )
    (comp (ref "D108")
      (value "WS2812 based digital RGB LED 2022 package")
      (footprint "LED_2022_WS2812B")
      (description "=Description")
      (libsource (lib "Phyx_Components") (part "LED_RGB_WS2812B_2022"))
    )
    (comp (ref "D109")
      (value "WS2812 based digital RGB LED 2022 package")
      (footprint "LED_2022_WS2812B")
      (description "=Description")
      (libsource (lib "Phyx_Components") (part "LED_RGB_WS2812B_2022"))
    )
    (comp (ref "D110")
      (value "WS2812 based digital RGB LED 2022 package")
      (footprint "LED_2022_WS2812B")
      (description "=Description")
      (libsource (lib "Phyx_Components") (part "LED_RGB_WS2812B_2022"))
    )
    (comp (ref "D111")
      (value "WS2812 based digital RGB LED 2022 package")
      (footprint "LED_2022_WS2812B")
      (description "=Description")
      (libsource (lib "Phyx_Components") (part "LED_RGB_WS2812B_2022"))
    )
    (comp (ref "D112")
      (value "WS2812 based digital RGB LED 2022 package")
      (footprint "LED_2022_WS2812B")
      (description "=Description")
      (libsource (lib "Phyx_Components") (part "LED_RGB_WS2812B_2022"))
    )
    (comp (ref "D113")
      (value "WS2812 based digital RGB LED 2022 package")
      (footprint "LED_2022_WS2812B")
      (description "=Description")
      (libsource (lib "Phyx_Components") (part "LED_RGB_WS2812B_2022"))
    )
    (comp (ref "D114")
      (value "WS2812 based digital RGB LED 2022 package")
      (footprint "LED_2022_WS2812B")
      (description "=Description")
      (libsource (lib "Phyx_Components") (part "LED_RGB_WS2812B_2022"))
    )
    (comp (ref "D115")
      (value "WS2812 based digital RGB LED 2022 package")
      (footprint "LED_2022_WS2812B")
      (description "=Description")
      (libsource (lib "Phyx_Components") (part "LED_RGB_WS2812B_2022"))
    )
    (comp (ref "D116")
      (value "WS2812 based digital RGB LED 2022 package")
      (footprint "LED_2022_WS2812B")
      (description "=Description")
      (libsource (lib "Phyx_Components") (part "LED_RGB_WS2812B_2022"))
    )
    (comp (ref "D117")
      (value "WS2812 based digital RGB LED 2022 package")
      (footprint "LED_2022_WS2812B")
      (description "=Description")
      (libsource (lib "Phyx_Components") (part "LED_RGB_WS2812B_2022"))
    )
    (comp (ref "D118")
      (value "WS2812 based digital RGB LED 2022 package")
      (footprint "LED_2022_WS2812B")
      (description "=Description")
      (libsource (lib "Phyx_Components") (part "LED_RGB_WS2812B_2022"))
    )
    (comp (ref "D119")
      (value "WS2812 based digital RGB LED 2022 package")
      (footprint "LED_2022_WS2812B")
      (description "=Description")
      (libsource (lib "Phyx_Components") (part "LED_RGB_WS2812B_2022"))
    )
    (comp (ref "D120")
      (value "WS2812 based digital RGB LED 2022 package")
      (footprint "LED_2022_WS2812B")
      (description "=Description")
      (libsource (lib "Phyx_Components") (part "LED_RGB_WS2812B_2022"))
    )
    (comp (ref "D121")
      (value "WS2812 based digital RGB LED 2022 package")
      (footprint "LED_2022_WS2812B")
      (description "=Description")
      (libsource (lib "Phyx_Components") (part "LED_RGB_WS2812B_2022"))
    )
    (comp (ref "D122")
      (value "WS2812 based digital RGB LED 2022 package")
      (footprint "LED_2022_WS2812B")
      (description "=Description")
      (libsource (lib "Phyx_Components") (part "LED_RGB_WS2812B_2022"))
    )
    (comp (ref "D123")
      (value "WS2812 based digital RGB LED 2022 package")
      (footprint "LED_2022_WS2812B")
      (description "=Description")
      (libsource (lib "Phyx_Components") (part "LED_RGB_WS2812B_2022"))
    )
    (comp (ref "D124")
      (value "WS2812 based digital RGB LED 2022 package")
      (footprint "LED_2022_WS2812B")
      (description "=Description")
      (libsource (lib "Phyx_Components") (part "LED_RGB_WS2812B_2022"))
    )
    (comp (ref "D125")
      (value "WS2812 based digital RGB LED 2022 package")
      (footprint "LED_2022_WS2812B")
      (description "=Description")
      (libsource (lib "Phyx_Components") (part "LED_RGB_WS2812B_2022"))
    )
    (comp (ref "D126")
      (value "WS2812 based digital RGB LED 2022 package")
      (footprint "LED_2022_WS2812B")
      (description "=Description")
      (libsource (lib "Phyx_Components") (part "LED_RGB_WS2812B_2022"))
    )
    (comp (ref "D127")
      (value "WS2812 based digital RGB LED 2022 package")
      (footprint "LED_2022_WS2812B")
      (description "=Description")
      (libsource (lib "Phyx_Components") (part "LED_RGB_WS2812B_2022"))
    )
    (comp (ref "D128")
      (value "WS2812 based digital RGB LED 2022 package")
      (footprint "LED_2022_WS2812B")
      (description "=Description")
      (libsource (lib "Phyx_Components") (part "LED_RGB_WS2812B_2022"))
    )
    (comp (ref "J1")
      (value "USB 2.0 C Reversible Receptacle Horizontal full SMD")
      (footprint "XUNPU-TYPEC-304S-ACP16")
      (libsource (lib "Phyx_Components") (part "USB_C_16_4"))
    )
    (comp (ref "P1")
      (value "Header 2")
      (footprint "HDR1X2")
      (libsource (lib "Phyx_Components") (part "Header 2"))
    )
    (comp (ref "P2")
      (value "Header 2")
      (footprint "HDR1X2")
      (libsource (lib "Phyx_Components") (part "Header 2"))
    )
    (comp (ref "R1")
      (value "10K")
      (footprint "R0603_N")
      (libsource (lib "Phyx_Components") (part "RESISTOR"))
    )
    (comp (ref "R2")
      (value "5K1")
      (footprint "R0603_N")
      (libsource (lib "Phyx_Components") (part "RESISTOR"))
    )
    (comp (ref "R3")
      (value "5K1")
      (footprint "R0603_N")
      (libsource (lib "Phyx_Components") (part "RESISTOR"))
    )
    (comp (ref "SW1")
      (value "LP SMD tact sw 3x2.5mm")
      (footprint "OMR_B3U-1000P")
      (libsource (lib "Phyx_Components") (part "SW_TACT"))
    )
    (comp (ref "U1")
      (value "CH32X035G8U6")
      (footprint "QFN_28_4.0x4.0_P0.4")
      (fields
        (field (name "Comment") "WCH CH32X035G8U6 QFN28 RISC-V 32-bit MCU, 62KB Flash, 10KB RAM, USB PD")
      )
      (libsource (lib "Phyx_Components") (part "WCH_CH32X035GxUx"))
    )
  )
  (nets
    (net (code "1") (name "/CC1") (class "Default")
      (node (ref "J1") (pin "A5") (pinfunction "CC1_A5") (pintype "passive"))
      (node (ref "R2") (pin "1") (pinfunction "1_1") (pintype "passive"))
    )
    (net (code "2") (name "/CC2") (class "Default")
      (node (ref "J1") (pin "B5") (pinfunction "CC2_B5") (pintype "passive"))
      (node (ref "R3") (pin "1") (pinfunction "1_1") (pintype "passive"))
    )
    (net (code "3") (name "/COL0") (class "Default")
      (node (ref "CZ1") (pin "2") (pinfunction "2_2") (pintype "passive"))
      (node (ref "CZ1") (pin "4") (pinfunction "4_4") (pintype "passive"))
      (node (ref "CZ1") (pin "6") (pinfunction "6_6") (pintype "passive"))
      (node (ref "CZ1") (pin "8") (pinfunction "8_8") (pintype "passive"))
      (node (ref "CZ3") (pin "2") (pinfunction "2_2") (pintype "passive"))
      (node (ref "CZ3") (pin "4") (pinfunction "4_4") (pintype "passive"))
      (node (ref "CZ3") (pin "6") (pinfunction "6_6") (pintype "passive"))
      (node (ref "CZ3") (pin "8") (pinfunction "8_8") (pintype "passive"))
      (node (ref "U1") (pin "3") (pinfunction "PC0_3") (pintype "bidirectional"))
    )
    (net (code "4") (name "/COL1") (class "Default")
      (node (ref "CZ1") (pin "10") (pinfunction "10_10") (pintype "passive"))
      (node (ref "CZ1") (pin "12") (pinfunction "12_12") (pintype "passive"))
      (node (ref "CZ1") (pin "14") (pinfunction "14_14") (pintype "passive"))
      (node (ref "CZ1") (pin "16") (pinfunction "16_16") (pintype "passive"))
      (node (ref "CZ3") (pin "10") (pinfunction "10_10") (pintype "passive"))
      (node (ref "CZ3") (pin "12") (pinfunction "12_12") (pintype "passive"))
      (node (ref "CZ3") (pin "14") (pinfunction "14_14") (pintype "passive"))
      (node (ref "CZ3") (pin "16") (pinfunction "16_16") (pintype "passive"))
      (node (ref "U1") (pin "4") (pinfunction "PC3_4") (pintype "bidirectional"))
    )
    (net (code "5") (name "/COL2") (class "Default")
      (node (ref "CZ1") (pin "18") (pinfunction "18_18") (pintype "passive"))
      (node (ref "CZ1") (pin "20") (pinfunction "20_20") (pintype "passive"))
      (node (ref "CZ1") (pin "22") (pinfunction "22_22") (pintype "passive"))
      (node (ref "CZ1") (pin "24") (pinfunction "24_24") (pintype "passive"))
      (node (ref "CZ3") (pin "18") (pinfunction "18_18") (pintype "passive"))
      (node (ref "CZ3") (pin "20") (pinfunction "20_20") (pintype "passive"))
      (node (ref "CZ3") (pin "22") (pinfunction "22_22") (pintype "passive"))
      (node (ref "CZ3") (pin "24") (pinfunction "24_24") (pintype "passive"))
      (node (ref "U1") (pin "5") (pinfunction "PA0_5") (pintype "bidirectional"))
    )
    (net (code "6") (name "/COL3") (class "Default")
      (node (ref "CZ1") (pin "26") (pinfunction "26_26") (pintype "passive"))
      (node (ref "CZ1") (pin "28") (pinfunction "28_28") (pintype "passive"))
      (node (ref "CZ1") (pin "30") (pinfunction "30_30") (pintype "passive"))
      (node (ref "CZ1") (pin "32") (pinfunction "32_32") (pintype "passive"))
      (node (ref "CZ3") (pin "26") (pinfunction "26_26") (pintype "passive"))
      (node (ref "CZ3") (pin "28") (pinfunction "28_28") (pintype "passive"))
      (node (ref "CZ3") (pin "30") (pinfunction "30_30") (pintype "passive"))
      (node (ref "CZ3") (pin "32") (pinfunction "32_32") (pintype "passive"))
      (node (ref "U1") (pin "6") (pinfunction "PA1_6") (pintype "bidirectional"))
    )
    (net (code "7") (name "/COL4") (class "Default")
      (node (ref "CZ2") (pin "2") (pinfunction "2_2") (pintype "passive"))
      (node (ref "CZ2") (pin "4") (pinfunction "4_4") (pintype "passive"))
      (node (ref "CZ2") (pin "6") (pinfunction "6_6") (pintype "passive"))
      (node (ref "CZ2") (pin "8") (pinfunction "8_8") (pintype "passive"))
      (node (ref "CZ4") (pin "2") (pinfunction "2_2") (pintype "passive"))
      (node (ref "CZ4") (pin "4") (pinfunction "4_4") (pintype "passive"))
      (node (ref "CZ4") (pin "6") (pinfunction "6_6") (pintype "passive"))
      (node (ref "CZ4") (pin "8") (pinfunction "8_8") (pintype "passive"))
      (node (ref "U1") (pin "7") (pinfunction "PA2_7") (pintype "bidirectional"))
    )
    (net (code "8") (name "/COL5") (class "Default")
      (node (ref "CZ2") (pin "10") (pinfunction "10_10") (pintype "passive"))
      (node (ref "CZ2") (pin "12") (pinfunction "12_12") (pintype "passive"))
      (node (ref "CZ2") (pin "14") (pinfunction "14_14") (pintype "passive"))
      (node (ref "CZ2") (pin "16") (pinfunction "16_16") (pintype "passive"))
      (node (ref "CZ4") (pin "10") (pinfunction "10_10") (pintype "passive"))
      (node (ref "CZ4") (pin "12") (pinfunction "12_12") (pintype "passive"))
      (node (ref "CZ4") (pin "14") (pinfunction "14_14") (pintype "passive"))
      (node (ref "CZ4") (pin "16") (pinfunction "16_16") (pintype "passive"))
      (node (ref "U1") (pin "8") (pinfunction "PA3_8") (pintype "bidirectional"))
    )
    (net (code "9") (name "/COL6") (class "Default")
      (node (ref "CZ2") (pin "18") (pinfunction "18_18") (pintype "passive"))
      (node (ref "CZ2") (pin "20") (pinfunction "20_20") (pintype "passive"))
      (node (ref "CZ2") (pin "22") (pinfunction "22_22") (pintype "passive"))
      (node (ref "CZ2") (pin "24") (pinfunction "24_24") (pintype "passive"))
      (node (ref "CZ4") (pin "18") (pinfunction "18_18") (pintype "passive"))
      (node (ref "CZ4") (pin "20") (pinfunction "20_20") (pintype "passive"))
      (node (ref "CZ4") (pin "22") (pinfunction "22_22") (pintype "passive"))
      (node (ref "CZ4") (pin "24") (pinfunction "24_24") (pintype "passive"))
      (node (ref "U1") (pin "9") (pinfunction "PA4/CS_9") (pintype "bidirectional"))
    )
    (net (code "10") (name "/COL7") (class "Default")
      (node (ref "CZ2") (pin "26") (pinfunction "26_26") (pintype "passive"))
      (node (ref "CZ2") (pin "28") (pinfunction "28_28") (pintype "passive"))
      (node (ref "CZ2") (pin "30") (pinfunction "30_30") (pintype "passive"))
      (node (ref "CZ2") (pin "32") (pinfunction "32_32") (pintype "passive"))
      (node (ref "CZ4") (pin "26") (pinfunction "26_26") (pintype "passive"))
      (node (ref "CZ4") (pin "28") (pinfunction "28_28") (pintype "passive"))
      (node (ref "CZ4") (pin "30") (pinfunction "30_30") (pintype "passive"))
      (node (ref "CZ4") (pin "32") (pinfunction "32_32") (pintype "passive"))
      (node (ref "U1") (pin "10") (pinfunction "PA5/SCK_10") (pintype "bidirectional"))
    )
    (net (code "11") (name "/IO.DCK") (class "Default")
      (node (ref "P1") (pin "1") (pinfunction "1_1") (pintype "passive"))
      (node (ref "U1") (pin "24") (pinfunction "PC19/DCK_24") (pintype "bidirectional"))
    )
    (net (code "12") (name "/IO.DIO") (class "Default")
      (node (ref "P1") (pin "2") (pinfunction "2_2") (pintype "passive"))
      (node (ref "U1") (pin "25") (pinfunction "PC18/DIO_25") (pintype "bidirectional"))
    )
    (net (code "13") (name "/LED.DIN") (class "Default")
      (node (ref "D1") (pin "3") (pinfunction "Di_3") (pintype "input"))
      (node (ref "U1") (pin "12") (pinfunction "PA7/MOSI_12") (pintype "bidirectional"))
    )
    (net (code "14") (name "/LED.DOUT") (class "Default")
      (node (ref "D128") (pin "1") (pinfunction "Do_1") (pintype "output"))
    )
    (net (code "15") (name "/ROW0") (class "Default")
      (node (ref "D17") (pin "A") (pinfunction "A_A") (pintype "passive"))
      (node (ref "D18") (pin "A") (pinfunction "A_A") (pintype "passive"))
      (node (ref "D33") (pin "A") (pinfunction "A_A") (pintype "passive"))
      (node (ref "D34") (pin "A") (pinfunction "A_A") (pintype "passive"))
      (node (ref "D49") (pin "A") (pinfunction "A_A") (pintype "passive"))
      (node (ref "D50") (pin "A") (pinfunction "A_A") (pintype "passive"))
      (node (ref "D65") (pin "A") (pinfunction "A_A") (pintype "passive"))
      (node (ref "D66") (pin "A") (pinfunction "A_A") (pintype "passive"))
      (node (ref "U1") (pin "23") (pinfunction "PB12_23") (pintype "bidirectional"))
    )
    (net (code "16") (name "/ROW1") (class "Default")
      (node (ref "D13") (pin "A") (pinfunction "A_A") (pintype "passive"))
      (node (ref "D14") (pin "A") (pinfunction "A_A") (pintype "passive"))
      (node (ref "D29") (pin "A") (pinfunction "A_A") (pintype "passive"))
      (node (ref "D30") (pin "A") (pinfunction "A_A") (pintype "passive"))
      (node (ref "D45") (pin "A") (pinfunction "A_A") (pintype "passive"))
      (node (ref "D46") (pin "A") (pinfunction "A_A") (pintype "passive"))
      (node (ref "D61") (pin "A") (pinfunction "A_A") (pintype "passive"))
      (node (ref "D62") (pin "A") (pinfunction "A_A") (pintype "passive"))
      (node (ref "U1") (pin "22") (pinfunction "PB11_22") (pintype "bidirectional"))
    )
    (net (code "17") (name "/ROW2") (class "Default")
      (node (ref "D10") (pin "A") (pinfunction "A_A") (pintype "passive"))
      (node (ref "D25") (pin "A") (pinfunction "A_A") (pintype "passive"))
      (node (ref "D26") (pin "A") (pinfunction "A_A") (pintype "passive"))
      (node (ref "D41") (pin "A") (pinfunction "A_A") (pintype "passive"))
      (node (ref "D42") (pin "A") (pinfunction "A_A") (pintype "passive"))
      (node (ref "D57") (pin "A") (pinfunction "A_A") (pintype "passive"))
      (node (ref "D58") (pin "A") (pinfunction "A_A") (pintype "passive"))
      (node (ref "D9") (pin "A") (pinfunction "A_A") (pintype "passive"))
      (node (ref "U1") (pin "21") (pinfunction "PB10_21") (pintype "bidirectional"))
    )
    (net (code "18") (name "/ROW3") (class "Default")
      (node (ref "D21") (pin "A") (pinfunction "A_A") (pintype "passive"))
      (node (ref "D22") (pin "A") (pinfunction "A_A") (pintype "passive"))
      (node (ref "D37") (pin "A") (pinfunction "A_A") (pintype "passive"))
      (node (ref "D38") (pin "A") (pinfunction "A_A") (pintype "passive"))
      (node (ref "D5") (pin "A") (pinfunction "A_A") (pintype "passive"))
      (node (ref "D53") (pin "A") (pinfunction "A_A") (pintype "passive"))
      (node (ref "D54") (pin "A") (pinfunction "A_A") (pintype "passive"))
      (node (ref "D6") (pin "A") (pinfunction "A_A") (pintype "passive"))
      (node (ref "U1") (pin "20") (pinfunction "PB9_20") (pintype "bidirectional"))
    )
    (net (code "19") (name "/ROW4") (class "Default")
      (node (ref "D19") (pin "A") (pinfunction "A_A") (pintype "passive"))
      (node (ref "D20") (pin "A") (pinfunction "A_A") (pintype "passive"))
      (node (ref "D35") (pin "A") (pinfunction "A_A") (pintype "passive"))
      (node (ref "D36") (pin "A") (pinfunction "A_A") (pintype "passive"))
      (node (ref "D51") (pin "A") (pinfunction "A_A") (pintype "passive"))
      (node (ref "D52") (pin "A") (pinfunction "A_A") (pintype "passive"))
      (node (ref "D67") (pin "A") (pinfunction "A_A") (pintype "passive"))
      (node (ref "D68") (pin "A") (pinfunction "A_A") (pintype "passive"))
      (node (ref "U1") (pin "19") (pinfunction "PB8_19") (pintype "bidirectional"))
    )
    (net (code "20") (name "/ROW5") (class "Default")
      (node (ref "D15") (pin "A") (pinfunction "A_A") (pintype "passive"))
      (node (ref "D16") (pin "A") (pinfunction "A_A") (pintype "passive"))
      (node (ref "D31") (pin "A") (pinfunction "A_A") (pintype "passive"))
      (node (ref "D32") (pin "A") (pinfunction "A_A") (pintype "passive"))
      (node (ref "D47") (pin "A") (pinfunction "A_A") (pintype "passive"))
      (node (ref "D48") (pin "A") (pinfunction "A_A") (pintype "passive"))
      (node (ref "D63") (pin "A") (pinfunction "A_A") (pintype "passive"))
      (node (ref "D64") (pin "A") (pinfunction "A_A") (pintype "passive"))
      (node (ref "U1") (pin "18") (pinfunction "PB7_18") (pintype "bidirectional"))
    )
    (net (code "21") (name "/ROW6") (class "Default")
      (node (ref "D11") (pin "A") (pinfunction "A_A") (pintype "passive"))
      (node (ref "D12") (pin "A") (pinfunction "A_A") (pintype "passive"))
      (node (ref "D27") (pin "A") (pinfunction "A_A") (pintype "passive"))
      (node (ref "D28") (pin "A") (pinfunction "A_A") (pintype "passive"))
      (node (ref "D43") (pin "A") (pinfunction "A_A") (pintype "passive"))
      (node (ref "D44") (pin "A") (pinfunction "A_A") (pintype "passive"))
      (node (ref "D59") (pin "A") (pinfunction "A_A") (pintype "passive"))
      (node (ref "D60") (pin "A") (pinfunction "A_A") (pintype "passive"))
      (node (ref "U1") (pin "17") (pinfunction "PB6_17") (pintype "bidirectional"))
    )
    (net (code "22") (name "/ROW7") (class "Default")
      (node (ref "D23") (pin "A") (pinfunction "A_A") (pintype "passive"))
      (node (ref "D24") (pin "A") (pinfunction "A_A") (pintype "passive"))
      (node (ref "D39") (pin "A") (pinfunction "A_A") (pintype "passive"))
      (node (ref "D40") (pin "A") (pinfunction "A_A") (pintype "passive"))
      (node (ref "D55") (pin "A") (pinfunction "A_A") (pintype "passive"))
      (node (ref "D56") (pin "A") (pinfunction "A_A") (pintype "passive"))
      (node (ref "D7") (pin "A") (pinfunction "A_A") (pintype "passive"))
      (node (ref "D8") (pin "A") (pinfunction "A_A") (pintype "passive"))
      (node (ref "U1") (pin "16") (pinfunction "PB1_16") (pintype "bidirectional"))
    )
    (net (code "23") (name "/USB.D_n") (class "Default")
      (node (ref "J1") (pin "A7") (pinfunction "Dn1_A7") (pintype "passive"))
      (node (ref "J1") (pin "B7") (pinfunction "Dn2_B7") (pintype "passive"))
      (node (ref "U1") (pin "26") (pinfunction "PC16/UD-_26") (pintype "bidirectional"))
    )
    (net (code "24") (name "/USB.D_p") (class "Default")
      (node (ref "J1") (pin "A6") (pinfunction "Dp1_A6") (pintype "passive"))
      (node (ref "J1") (pin "B6") (pinfunction "Dp2_B6") (pintype "passive"))
      (node (ref "SW1") (pin "2") (pinfunction "2_2") (pintype "passive"))
      (node (ref "U1") (pin "27") (pinfunction "PC17/UD+_27") (pintype "bidirectional"))
    )
    (net (code "25") (name "GND") (class "Default")
      (node (ref "C1") (pin "2") (pinfunction "2_2") (pintype "passive"))
      (node (ref "C10") (pin "2") (pinfunction "2_2") (pintype "passive"))
      (node (ref "C11") (pin "2") (pinfunction "2_2") (pintype "passive"))
      (node (ref "C12") (pin "2") (pinfunction "2_2") (pintype "passive"))
      (node (ref "C13") (pin "2") (pinfunction "2_2") (pintype "passive"))
      (node (ref "C14") (pin "2") (pinfunction "2_2") (pintype "passive"))
      (node (ref "C15") (pin "2") (pinfunction "2_2") (pintype "passive"))
      (node (ref "C16") (pin "2") (pinfunction "2_2") (pintype "passive"))
      (node (ref "C17") (pin "2") (pinfunction "2_2") (pintype "passive"))
      (node (ref "C18") (pin "2") (pinfunction "2_2") (pintype "passive"))
      (node (ref "C19") (pin "2") (pinfunction "2_2") (pintype "passive"))
      (node (ref "C2") (pin "2") (pinfunction "2_2") (pintype "passive"))
      (node (ref "C20") (pin "2") (pinfunction "2_2") (pintype "passive"))
      (node (ref "C21") (pin "2") (pinfunction "2_2") (pintype "passive"))
      (node (ref "C22") (pin "2") (pinfunction "2_2") (pintype "passive"))
      (node (ref "C23") (pin "2") (pinfunction "2_2") (pintype "passive"))
      (node (ref "C24") (pin "2") (pinfunction "2_2") (pintype "passive"))
      (node (ref "C25") (pin "2") (pinfunction "2_2") (pintype "passive"))
      (node (ref "C26") (pin "2") (pinfunction "2_2") (pintype "passive"))
      (node (ref "C27") (pin "2") (pinfunction "2_2") (pintype "passive"))
      (node (ref "C28") (pin "2") (pinfunction "2_2") (pintype "passive"))
      (node (ref "C29") (pin "2") (pinfunction "2_2") (pintype "passive"))
      (node (ref "C3") (pin "2") (pinfunction "2_2") (pintype "passive"))
      (node (ref "C30") (pin "2") (pinfunction "2_2") (pintype "passive"))
      (node (ref "C31") (pin "2") (pinfunction "2_2") (pintype "passive"))
      (node (ref "C32") (pin "2") (pinfunction "2_2") (pintype "passive"))
      (node (ref "C33") (pin "2") (pinfunction "2_2") (pintype "passive"))
      (node (ref "C34") (pin "2") (pinfunction "2_2") (pintype "passive"))
      (node (ref "C35") (pin "2") (pinfunction "2_2") (pintype "passive"))
      (node (ref "C36") (pin "2") (pinfunction "2_2") (pintype "passive"))
      (node (ref "C37") (pin "2") (pinfunction "2_2") (pintype "passive"))
      (node (ref "C38") (pin "2") (pinfunction "2_2") (pintype "passive"))
      (node (ref "C39") (pin "2") (pinfunction "2_2") (pintype "passive"))
      (node (ref "C4") (pin "2") (pinfunction "2_2") (pintype "passive"))
      (node (ref "C40") (pin "2") (pinfunction "2_2") (pintype "passive"))
      (node (ref "C41") (pin "2") (pinfunction "2_2") (pintype "passive"))
      (node (ref "C42") (pin "2") (pinfunction "2_2") (pintype "passive"))
      (node (ref "C43") (pin "2") (pinfunction "2_2") (pintype "passive"))
      (node (ref "C44") (pin "2") (pinfunction "2_2") (pintype "passive"))
      (node (ref "C45") (pin "2") (pinfunction "2_2") (pintype "passive"))
      (node (ref "C46") (pin "2") (pinfunction "2_2") (pintype "passive"))
      (node (ref "C47") (pin "2") (pinfunction "2_2") (pintype "passive"))
      (node (ref "C48") (pin "2") (pinfunction "2_2") (pintype "passive"))
      (node (ref "C49") (pin "2") (pinfunction "2_2") (pintype "passive"))
      (node (ref "C5") (pin "2") (pinfunction "2_2") (pintype "passive"))
      (node (ref "C50") (pin "2") (pinfunction "2_2") (pintype "passive"))
      (node (ref "C51") (pin "2") (pinfunction "2_2") (pintype "passive"))
      (node (ref "C52") (pin "2") (pinfunction "2_2") (pintype "passive"))
      (node (ref "C53") (pin "2") (pinfunction "2_2") (pintype "passive"))
      (node (ref "C54") (pin "2") (pinfunction "2_2") (pintype "passive"))
      (node (ref "C55") (pin "2") (pinfunction "2_2") (pintype "passive"))
      (node (ref "C56") (pin "2") (pinfunction "2_2") (pintype "passive"))
      (node (ref "C57") (pin "2") (pinfunction "2_2") (pintype "passive"))
      (node (ref "C58") (pin "2") (pinfunction "2_2") (pintype "passive"))
      (node (ref "C59") (pin "2") (pinfunction "2_2") (pintype "passive"))
      (node (ref "C6") (pin "2") (pinfunction "2_2") (pintype "passive"))
      (node (ref "C60") (pin "2") (pinfunction "2_2") (pintype "passive"))
      (node (ref "C61") (pin "2") (pinfunction "2_2") (pintype "passive"))
      (node (ref "C62") (pin "2") (pinfunction "2_2") (pintype "passive"))
      (node (ref "C63") (pin "2") (pinfunction "2_2") (pintype "passive"))
      (node (ref "C64") (pin "2") (pinfunction "2_2") (pintype "passive"))
      (node (ref "C65") (pin "2") (pinfunction "2_2") (pintype "passive"))
      (node (ref "C66") (pin "2") (pinfunction "2_2") (pintype "passive"))
      (node (ref "C7") (pin "2") (pinfunction "2_2") (pintype "passive"))
      (node (ref "C8") (pin "2") (pinfunction "2_2") (pintype "passive"))
      (node (ref "C9") (pin "2") (pinfunction "2_2") (pintype "passive"))
      (node (ref "D1") (pin "2") (pinfunction "G_2") (pintype "power_in"))
      (node (ref "D100") (pin "2") (pinfunction "G_2") (pintype "power_in"))
      (node (ref "D101") (pin "2") (pinfunction "G_2") (pintype "power_in"))
      (node (ref "D102") (pin "2") (pinfunction "G_2") (pintype "power_in"))
      (node (ref "D103") (pin "2") (pinfunction "G_2") (pintype "power_in"))
      (node (ref "D104") (pin "2") (pinfunction "G_2") (pintype "power_in"))
      (node (ref "D105") (pin "2") (pinfunction "G_2") (pintype "power_in"))
      (node (ref "D106") (pin "2") (pinfunction "G_2") (pintype "power_in"))
      (node (ref "D107") (pin "2") (pinfunction "G_2") (pintype "power_in"))
      (node (ref "D108") (pin "2") (pinfunction "G_2") (pintype "power_in"))
      (node (ref "D109") (pin "2") (pinfunction "G_2") (pintype "power_in"))
      (node (ref "D110") (pin "2") (pinfunction "G_2") (pintype "power_in"))
      (node (ref "D111") (pin "2") (pinfunction "G_2") (pintype "power_in"))
      (node (ref "D112") (pin "2") (pinfunction "G_2") (pintype "power_in"))
      (node (ref "D113") (pin "2") (pinfunction "G_2") (pintype "power_in"))
      (node (ref "D114") (pin "2") (pinfunction "G_2") (pintype "power_in"))
      (node (ref "D115") (pin "2") (pinfunction "G_2") (pintype "power_in"))
      (node (ref "D116") (pin "2") (pinfunction "G_2") (pintype "power_in"))
      (node (ref "D117") (pin "2") (pinfunction "G_2") (pintype "power_in"))
      (node (ref "D118") (pin "2") (pinfunction "G_2") (pintype "power_in"))
      (node (ref "D119") (pin "2") (pinfunction "G_2") (pintype "power_in"))
      (node (ref "D120") (pin "2") (pinfunction "G_2") (pintype "power_in"))
      (node (ref "D121") (pin "2") (pinfunction "G_2") (pintype "power_in"))
      (node (ref "D122") (pin "2") (pinfunction "G_2") (pintype "power_in"))
      (node (ref "D123") (pin "2") (pinfunction "G_2") (pintype "power_in"))
      (node (ref "D124") (pin "2") (pinfunction "G_2") (pintype "power_in"))
      (node (ref "D125") (pin "2") (pinfunction "G_2") (pintype "power_in"))
      (node (ref "D126") (pin "2") (pinfunction "G_2") (pintype "power_in"))
      (node (ref "D127") (pin "2") (pinfunction "G_2") (pintype "power_in"))
      (node (ref "D128") (pin "2") (pinfunction "G_2") (pintype "power_in"))
      (node (ref "D2") (pin "2") (pinfunction "G_2") (pintype "power_in"))
      (node (ref "D3") (pin "2") (pinfunction "G_2") (pintype "power_in"))
      (node (ref "D4") (pin "2") (pinfunction "G_2") (pintype "power_in"))
      (node (ref "D69") (pin "2") (pinfunction "G_2") (pintype "power_in"))
      (node (ref "D70") (pin "2") (pinfunction "G_2") (pintype "power_in"))
      (node (ref "D71") (pin "2") (pinfunction "G_2") (pintype "power_in"))
      (node (ref "D72") (pin "2") (pinfunction "G_2") (pintype "power_in"))
      (node (ref "D73") (pin "2") (pinfunction "G_2") (pintype "power_in"))
      (node (ref "D74") (pin "2") (pinfunction "G_2") (pintype "power_in"))
      (node (ref "D75") (pin "2") (pinfunction "G_2") (pintype "power_in"))
      (node (ref "D76") (pin "2") (pinfunction "G_2") (pintype "power_in"))
      (node (ref "D77") (pin "2") (pinfunction "G_2") (pintype "power_in"))
      (node (ref "D78") (pin "2") (pinfunction "G_2") (pintype "power_in"))
      (node (ref "D79") (pin "2") (pinfunction "G_2") (pintype "power_in"))
      (node (ref "D80") (pin "2") (pinfunction "G_2") (pintype "power_in"))
      (node (ref "D81") (pin "2") (pinfunction "G_2") (pintype "power_in"))
      (node (ref "D82") (pin "2") (pinfunction "G_2") (pintype "power_in"))
      (node (ref "D83") (pin "2") (pinfunction "G_2") (pintype "power_in"))
      (node (ref "D84") (pin "2") (pinfunction "G_2") (pintype "power_in"))
      (node (ref "D85") (pin "2") (pinfunction "G_2") (pintype "power_in"))
      (node (ref "D86") (pin "2") (pinfunction "G_2") (pintype "power_in"))
      (node (ref "D87") (pin "2") (pinfunction "G_2") (pintype "power_in"))
      (node (ref "D88") (pin "2") (pinfunction "G_2") (pintype "power_in"))
      (node (ref "D89") (pin "2") (pinfunction "G_2") (pintype "power_in"))
      (node (ref "D90") (pin "2") (pinfunction "G_2") (pintype "power_in"))
      (node (ref "D91") (pin "2") (pinfunction "G_2") (pintype "power_in"))
      (node (ref "D92") (pin "2") (pinfunction "G_2") (pintype "power_in"))
      (node (ref "D93") (pin "2") (pinfunction "G_2") (pintype "power_in"))
      (node (ref "D94") (pin "2") (pinfunction "G_2") (pintype "power_in"))
      (node (ref "D95") (pin "2") (pinfunction "G_2") (pintype "power_in"))
      (node (ref "D96") (pin "2") (pinfunction "G_2") (pintype "power_in"))
      (node (ref "D97") (pin "2") (pinfunction "G_2") (pintype "power_in"))
      (node (ref "D98") (pin "2") (pinfunction "G_2") (pintype "power_in"))
      (node (ref "D99") (pin "2") (pinfunction "G_2") (pintype "power_in"))
      (node (ref "J1") (pin "A1") (pinfunction "GND_A1") (pintype "passive"))
      (node (ref "J1") (pin "A12") (pinfunction "GND_A12") (pintype "passive"))
      (node (ref "J1") (pin "B1") (pinfunction "GND_B1") (pintype "passive"))
      (node (ref "J1") (pin "B12") (pinfunction "GND_B12") (pintype "passive"))
      (node (ref "J1") (pin "MH1") (pinfunction "Tab_MH1") (pintype "passive"))
      (node (ref "J1") (pin "MH2") (pinfunction "Tab_MH2") (pintype "passive"))
      (node (ref "J1") (pin "MH3") (pinfunction "Tab_MH3") (pintype "passive"))
      (node (ref "J1") (pin "MH4") (pinfunction "Tab_MH4") (pintype "passive"))
      (node (ref "P2") (pin "1") (pinfunction "1_1") (pintype "passive"))
      (node (ref "R2") (pin "2") (pinfunction "2_2") (pintype "passive"))
      (node (ref "R3") (pin "2") (pinfunction "2_2") (pintype "passive"))
      (node (ref "U1") (pin "29") (pinfunction "GND_29") (pintype "power_in"))
    )
    (net (code "26") (name "Net-(CZ1-Pad1)") (class "Default")
      (node (ref "CZ1") (pin "1") (pinfunction "1_1") (pintype "passive"))
      (node (ref "D17") (pin "C") (pinfunction "C_C") (pintype "passive"))
    )
    (net (code "27") (name "Net-(CZ1-Pad3)") (class "Default")
      (node (ref "CZ1") (pin "3") (pinfunction "3_3") (pintype "passive"))
      (node (ref "D13") (pin "C") (pinfunction "C_C") (pintype "passive"))
    )
    (net (code "28") (name "Net-(CZ1-Pad5)") (class "Default")
      (node (ref "CZ1") (pin "5") (pinfunction "5_5") (pintype "passive"))
      (node (ref "D9") (pin "C") (pinfunction "C_C") (pintype "passive"))
    )
    (net (code "29") (name "Net-(CZ1-Pad7)") (class "Default")
      (node (ref "CZ1") (pin "7") (pinfunction "7_7") (pintype "passive"))
      (node (ref "D5") (pin "C") (pinfunction "C_C") (pintype "passive"))
    )
    (net (code "30") (name "Net-(CZ1-Pad9)") (class "Default")
      (node (ref "CZ1") (pin "9") (pinfunction "9_9") (pintype "passive"))
      (node (ref "D33") (pin "C") (pinfunction "C_C") (pintype "passive"))
    )
    (net (code "31") (name "Net-(CZ1-Pad11)") (class "Default")
      (node (ref "CZ1") (pin "11") (pinfunction "11_11") (pintype "passive"))
      (node (ref "D29") (pin "C") (pinfunction "C_C") (pintype "passive"))
    )
    (net (code "32") (name "Net-(CZ1-Pad13)") (class "Default")
      (node (ref "CZ1") (pin "13") (pinfunction "13_13") (pintype "passive"))
      (node (ref "D25") (pin "C") (pinfunction "C_C") (pintype "passive"))
    )
    (net (code "33") (name "Net-(CZ1-Pad15)") (class "Default")
      (node (ref "CZ1") (pin "15") (pinfunction "15_15") (pintype "passive"))
      (node (ref "D21") (pin "C") (pinfunction "C_C") (pintype "passive"))
    )
    (net (code "34") (name "Net-(CZ1-Pad17)") (class "Default")
      (node (ref "CZ1") (pin "17") (pinfunction "17_17") (pintype "passive"))
      (node (ref "D49") (pin "C") (pinfunction "C_C") (pintype "passive"))
    )
    (net (code "35") (name "Net-(CZ1-Pad19)") (class "Default")
      (node (ref "CZ1") (pin "19") (pinfunction "19_19") (pintype "passive"))
      (node (ref "D45") (pin "C") (pinfunction "C_C") (pintype "passive"))
    )
    (net (code "36") (name "Net-(CZ1-Pad21)") (class "Default")
      (node (ref "CZ1") (pin "21") (pinfunction "21_21") (pintype "passive"))
      (node (ref "D41") (pin "C") (pinfunction "C_C") (pintype "passive"))
    )
    (net (code "37") (name "Net-(CZ1-Pad23)") (class "Default")
      (node (ref "CZ1") (pin "23") (pinfunction "23_23") (pintype "passive"))
      (node (ref "D37") (pin "C") (pinfunction "C_C") (pintype "passive"))
    )
    (net (code "38") (name "Net-(CZ1-Pad25)") (class "Default")
      (node (ref "CZ1") (pin "25") (pinfunction "25_25") (pintype "passive"))
      (node (ref "D65") (pin "C") (pinfunction "C_C") (pintype "passive"))
    )
    (net (code "39") (name "Net-(CZ1-Pad27)") (class "Default")
      (node (ref "CZ1") (pin "27") (pinfunction "27_27") (pintype "passive"))
      (node (ref "D61") (pin "C") (pinfunction "C_C") (pintype "passive"))
    )
    (net (code "40") (name "Net-(CZ1-Pad29)") (class "Default")
      (node (ref "CZ1") (pin "29") (pinfunction "29_29") (pintype "passive"))
      (node (ref "D57") (pin "C") (pinfunction "C_C") (pintype "passive"))
    )
    (net (code "41") (name "Net-(CZ1-Pad31)") (class "Default")
      (node (ref "CZ1") (pin "31") (pinfunction "31_31") (pintype "passive"))
      (node (ref "D53") (pin "C") (pinfunction "C_C") (pintype "passive"))
    )
    (net (code "42") (name "Net-(CZ2-Pad1)") (class "Default")
      (node (ref "CZ2") (pin "1") (pinfunction "1_1") (pintype "passive"))
      (node (ref "D18") (pin "C") (pinfunction "C_C") (pintype "passive"))
    )
    (net (code "43") (name "Net-(CZ2-Pad3)") (class "Default")
      (node (ref "CZ2") (pin "3") (pinfunction "3_3") (pintype "passive"))
      (node (ref "D14") (pin "C") (pinfunction "C_C") (pintype "passive"))
    )
    (net (code "44") (name "Net-(CZ2-Pad5)") (class "Default")
      (node (ref "CZ2") (pin "5") (pinfunction "5_5") (pintype "passive"))
      (node (ref "D10") (pin "C") (pinfunction "C_C") (pintype "passive"))
    )
    (net (code "45") (name "Net-(CZ2-Pad7)") (class "Default")
      (node (ref "CZ2") (pin "7") (pinfunction "7_7") (pintype "passive"))
      (node (ref "D6") (pin "C") (pinfunction "C_C") (pintype "passive"))
    )
    (net (code "46") (name "Net-(CZ2-Pad9)") (class "Default")
      (node (ref "CZ2") (pin "9") (pinfunction "9_9") (pintype "passive"))
      (node (ref "D34") (pin "C") (pinfunction "C_C") (pintype "passive"))
    )
    (net (code "47") (name "Net-(CZ2-Pad11)") (class "Default")
      (node (ref "CZ2") (pin "11") (pinfunction "11_11") (pintype "passive"))
      (node (ref "D30") (pin "C") (pinfunction "C_C") (pintype "passive"))
    )
    (net (code "48") (name "Net-(CZ2-Pad13)") (class "Default")
      (node (ref "CZ2") (pin "13") (pinfunction "13_13") (pintype "passive"))
      (node (ref "D26") (pin "C") (pinfunction "C_C") (pintype "passive"))
    )
    (net (code "49") (name "Net-(CZ2-Pad15)") (class "Default")
      (node (ref "CZ2") (pin "15") (pinfunction "15_15") (pintype "passive"))
      (node (ref "D22") (pin "C") (pinfunction "C_C") (pintype "passive"))
    )
    (net (code "50") (name "Net-(CZ2-Pad17)") (class "Default")
      (node (ref "CZ2") (pin "17") (pinfunction "17_17") (pintype "passive"))
      (node (ref "D50") (pin "C") (pinfunction "C_C") (pintype "passive"))
    )
    (net (code "51") (name "Net-(CZ2-Pad19)") (class "Default")
      (node (ref "CZ2") (pin "19") (pinfunction "19_19") (pintype "passive"))
      (node (ref "D46") (pin "C") (pinfunction "C_C") (pintype "passive"))
    )
    (net (code "52") (name "Net-(CZ2-Pad21)") (class "Default")
      (node (ref "CZ2") (pin "21") (pinfunction "21_21") (pintype "passive"))
      (node (ref "D42") (pin "C") (pinfunction "C_C") (pintype "passive"))
    )
    (net (code "53") (name "Net-(CZ2-Pad23)") (class "Default")
      (node (ref "CZ2") (pin "23") (pinfunction "23_23") (pintype "passive"))
      (node (ref "D38") (pin "C") (pinfunction "C_C") (pintype "passive"))
    )
    (net (code "54") (name "Net-(CZ2-Pad25)") (class "Default")
      (node (ref "CZ2") (pin "25") (pinfunction "25_25") (pintype "passive"))
      (node (ref "D66") (pin "C") (pinfunction "C_C") (pintype "passive"))
    )
    (net (code "55") (name "Net-(CZ2-Pad27)") (class "Default")
      (node (ref "CZ2") (pin "27") (pinfunction "27_27") (pintype "passive"))
      (node (ref "D62") (pin "C") (pinfunction "C_C") (pintype "passive"))
    )
    (net (code "56") (name "Net-(CZ2-Pad29)") (class "Default")
      (node (ref "CZ2") (pin "29") (pinfunction "29_29") (pintype "passive"))
      (node (ref "D58") (pin "C") (pinfunction "C_C") (pintype "passive"))
    )
    (net (code "57") (name "Net-(CZ2-Pad31)") (class "Default")
      (node (ref "CZ2") (pin "31") (pinfunction "31_31") (pintype "passive"))
      (node (ref "D54") (pin "C") (pinfunction "C_C") (pintype "passive"))
    )
    (net (code "58") (name "Net-(CZ3-Pad1)") (class "Default")
      (node (ref "CZ3") (pin "1") (pinfunction "1_1") (pintype "passive"))
      (node (ref "D19") (pin "C") (pinfunction "C_C") (pintype "passive"))
    )
    (net (code "59") (name "Net-(CZ3-Pad3)") (class "Default")
      (node (ref "CZ3") (pin "3") (pinfunction "3_3") (pintype "passive"))
      (node (ref "D15") (pin "C") (pinfunction "C_C") (pintype "passive"))
    )
    (net (code "60") (name "Net-(CZ3-Pad5)") (class "Default")
      (node (ref "CZ3") (pin "5") (pinfunction "5_5") (pintype "passive"))
      (node (ref "D11") (pin "C") (pinfunction "C_C") (pintype "passive"))
    )
    (net (code "61") (name "Net-(CZ3-Pad7)") (class "Default")
      (node (ref "CZ3") (pin "7") (pinfunction "7_7") (pintype "passive"))
      (node (ref "D7") (pin "C") (pinfunction "C_C") (pintype "passive"))
    )
    (net (code "62") (name "Net-(CZ3-Pad9)") (class "Default")
      (node (ref "CZ3") (pin "9") (pinfunction "9_9") (pintype "passive"))
      (node (ref "D35") (pin "C") (pinfunction "C_C") (pintype "passive"))
    )
    (net (code "63") (name "Net-(CZ3-Pad11)") (class "Default")
      (node (ref "CZ3") (pin "11") (pinfunction "11_11") (pintype "passive"))
      (node (ref "D31") (pin "C") (pinfunction "C_C") (pintype "passive"))
    )
    (net (code "64") (name "Net-(CZ3-Pad13)") (class "Default")
      (node (ref "CZ3") (pin "13") (pinfunction "13_13") (pintype "passive"))
      (node (ref "D27") (pin "C") (pinfunction "C_C") (pintype "passive"))
    )
    (net (code "65") (name "Net-(CZ3-Pad15)") (class "Default")
      (node (ref "CZ3") (pin "15") (pinfunction "15_15") (pintype "passive"))
      (node (ref "D23") (pin "C") (pinfunction "C_C") (pintype "passive"))
    )
    (net (code "66") (name "Net-(CZ3-Pad17)") (class "Default")
      (node (ref "CZ3") (pin "17") (pinfunction "17_17") (pintype "passive"))
      (node (ref "D51") (pin "C") (pinfunction "C_C") (pintype "passive"))
    )
    (net (code "67") (name "Net-(CZ3-Pad19)") (class "Default")
      (node (ref "CZ3") (pin "19") (pinfunction "19_19") (pintype "passive"))
      (node (ref "D47") (pin "C") (pinfunction "C_C") (pintype "passive"))
    )
    (net (code "68") (name "Net-(CZ3-Pad21)") (class "Default")
      (node (ref "CZ3") (pin "21") (pinfunction "21_21") (pintype "passive"))
      (node (ref "D43") (pin "C") (pinfunction "C_C") (pintype "passive"))
    )
    (net (code "69") (name "Net-(CZ3-Pad23)") (class "Default")
      (node (ref "CZ3") (pin "23") (pinfunction "23_23") (pintype "passive"))
      (node (ref "D39") (pin "C") (pinfunction "C_C") (pintype "passive"))
    )
    (net (code "70") (name "Net-(CZ3-Pad25)") (class "Default")
      (node (ref "CZ3") (pin "25") (pinfunction "25_25") (pintype "passive"))
      (node (ref "D67") (pin "C") (pinfunction "C_C") (pintype "passive"))
    )
    (net (code "71") (name "Net-(CZ3-Pad27)") (class "Default")
      (node (ref "CZ3") (pin "27") (pinfunction "27_27") (pintype "passive"))
      (node (ref "D63") (pin "C") (pinfunction "C_C") (pintype "passive"))
    )
    (net (code "72") (name "Net-(CZ3-Pad29)") (class "Default")
      (node (ref "CZ3") (pin "29") (pinfunction "29_29") (pintype "passive"))
      (node (ref "D59") (pin "C") (pinfunction "C_C") (pintype "passive"))
    )
    (net (code "73") (name "Net-(CZ3-Pad31)") (class "Default")
      (node (ref "CZ3") (pin "31") (pinfunction "31_31") (pintype "passive"))
      (node (ref "D55") (pin "C") (pinfunction "C_C") (pintype "passive"))
    )
    (net (code "74") (name "Net-(CZ4-Pad1)") (class "Default")
      (node (ref "CZ4") (pin "1") (pinfunction "1_1") (pintype "passive"))
      (node (ref "D20") (pin "C") (pinfunction "C_C") (pintype "passive"))
    )
    (net (code "75") (name "Net-(CZ4-Pad3)") (class "Default")
      (node (ref "CZ4") (pin "3") (pinfunction "3_3") (pintype "passive"))
      (node (ref "D16") (pin "C") (pinfunction "C_C") (pintype "passive"))
    )
    (net (code "76") (name "Net-(CZ4-Pad5)") (class "Default")
      (node (ref "CZ4") (pin "5") (pinfunction "5_5") (pintype "passive"))
      (node (ref "D12") (pin "C") (pinfunction "C_C") (pintype "passive"))
    )
    (net (code "77") (name "Net-(CZ4-Pad7)") (class "Default")
      (node (ref "CZ4") (pin "7") (pinfunction "7_7") (pintype "passive"))
      (node (ref "D8") (pin "C") (pinfunction "C_C") (pintype "passive"))
    )
    (net (code "78") (name "Net-(CZ4-Pad9)") (class "Default")
      (node (ref "CZ4") (pin "9") (pinfunction "9_9") (pintype "passive"))
      (node (ref "D36") (pin "C") (pinfunction "C_C") (pintype "passive"))
    )
    (net (code "79") (name "Net-(CZ4-Pad11)") (class "Default")
      (node (ref "CZ4") (pin "11") (pinfunction "11_11") (pintype "passive"))
      (node (ref "D32") (pin "C") (pinfunction "C_C") (pintype "passive"))
    )
    (net (code "80") (name "Net-(CZ4-Pad13)") (class "Default")
      (node (ref "CZ4") (pin "13") (pinfunction "13_13") (pintype "passive"))
      (node (ref "D28") (pin "C") (pinfunction "C_C") (pintype "passive"))
    )
    (net (code "81") (name "Net-(CZ4-Pad15)") (class "Default")
      (node (ref "CZ4") (pin "15") (pinfunction "15_15") (pintype "passive"))
      (node (ref "D24") (pin "C") (pinfunction "C_C") (pintype "passive"))
    )
    (net (code "82") (name "Net-(CZ4-Pad17)") (class "Default")
      (node (ref "CZ4") (pin "17") (pinfunction "17_17") (pintype "passive"))
      (node (ref "D52") (pin "C") (pinfunction "C_C") (pintype "passive"))
    )
    (net (code "83") (name "Net-(CZ4-Pad19)") (class "Default")
      (node (ref "CZ4") (pin "19") (pinfunction "19_19") (pintype "passive"))
      (node (ref "D48") (pin "C") (pinfunction "C_C") (pintype "passive"))
    )
    (net (code "84") (name "Net-(CZ4-Pad21)") (class "Default")
      (node (ref "CZ4") (pin "21") (pinfunction "21_21") (pintype "passive"))
      (node (ref "D44") (pin "C") (pinfunction "C_C") (pintype "passive"))
    )
    (net (code "85") (name "Net-(CZ4-Pad23)") (class "Default")
      (node (ref "CZ4") (pin "23") (pinfunction "23_23") (pintype "passive"))
      (node (ref "D40") (pin "C") (pinfunction "C_C") (pintype "passive"))
    )
    (net (code "86") (name "Net-(CZ4-Pad25)") (class "Default")
      (node (ref "CZ4") (pin "25") (pinfunction "25_25") (pintype "passive"))
      (node (ref "D68") (pin "C") (pinfunction "C_C") (pintype "passive"))
    )
    (net (code "87") (name "Net-(CZ4-Pad27)") (class "Default")
      (node (ref "CZ4") (pin "27") (pinfunction "27_27") (pintype "passive"))
      (node (ref "D64") (pin "C") (pinfunction "C_C") (pintype "passive"))
    )
    (net (code "88") (name "Net-(CZ4-Pad29)") (class "Default")
      (node (ref "CZ4") (pin "29") (pinfunction "29_29") (pintype "passive"))
      (node (ref "D60") (pin "C") (pinfunction "C_C") (pintype "passive"))
    )
    (net (code "89") (name "Net-(CZ4-Pad31)") (class "Default")
      (node (ref "CZ4") (pin "31") (pinfunction "31_31") (pintype "passive"))
      (node (ref "D56") (pin "C") (pinfunction "C_C") (pintype "passive"))
    )
    (net (code "90") (name "Net-(D1-Do)") (class "Default")
      (node (ref "D1") (pin "1") (pinfunction "Do_1") (pintype "output"))
      (node (ref "D2") (pin "3") (pinfunction "Di_3") (pintype "input"))
    )
    (net (code "91") (name "Net-(D2-Do)") (class "Default")
      (node (ref "D2") (pin "1") (pinfunction "Do_1") (pintype "output"))
      (node (ref "D3") (pin "3") (pinfunction "Di_3") (pintype "input"))
    )
    (net (code "92") (name "Net-(D3-Do)") (class "Default")
      (node (ref "D3") (pin "1") (pinfunction "Do_1") (pintype "output"))
      (node (ref "D4") (pin "3") (pinfunction "Di_3") (pintype "input"))
    )
    (net (code "93") (name "Net-(D4-Do)") (class "Default")
      (node (ref "D4") (pin "1") (pinfunction "Do_1") (pintype "output"))
      (node (ref "D69") (pin "3") (pinfunction "Di_3") (pintype "input"))
    )
    (net (code "94") (name "Net-(D69-Do)") (class "Default")
      (node (ref "D69") (pin "1") (pinfunction "Do_1") (pintype "output"))
      (node (ref "D70") (pin "3") (pinfunction "Di_3") (pintype "input"))
    )
    (net (code "95") (name "Net-(D70-Do)") (class "Default")
      (node (ref "D70") (pin "1") (pinfunction "Do_1") (pintype "output"))
      (node (ref "D71") (pin "3") (pinfunction "Di_3") (pintype "input"))
    )
    (net (code "96") (name "Net-(D71-Do)") (class "Default")
      (node (ref "D71") (pin "1") (pinfunction "Do_1") (pintype "output"))
      (node (ref "D72") (pin "3") (pinfunction "Di_3") (pintype "input"))
    )
    (net (code "97") (name "Net-(D72-Do)") (class "Default")
      (node (ref "D72") (pin "1") (pinfunction "Do_1") (pintype "output"))
      (node (ref "D73") (pin "3") (pinfunction "Di_3") (pintype "input"))
    )
    (net (code "98") (name "Net-(D73-Do)") (class "Default")
      (node (ref "D73") (pin "1") (pinfunction "Do_1") (pintype "output"))
      (node (ref "D74") (pin "3") (pinfunction "Di_3") (pintype "input"))
    )
    (net (code "99") (name "Net-(D74-Do)") (class "Default")
      (node (ref "D74") (pin "1") (pinfunction "Do_1") (pintype "output"))
      (node (ref "D75") (pin "3") (pinfunction "Di_3") (pintype "input"))
    )
    (net (code "100") (name "Net-(D75-Do)") (class "Default")
      (node (ref "D75") (pin "1") (pinfunction "Do_1") (pintype "output"))
      (node (ref "D76") (pin "3") (pinfunction "Di_3") (pintype "input"))
    )
    (net (code "101") (name "Net-(D76-Do)") (class "Default")
      (node (ref "D76") (pin "1") (pinfunction "Do_1") (pintype "output"))
      (node (ref "D77") (pin "3") (pinfunction "Di_3") (pintype "input"))
    )
    (net (code "102") (name "Net-(D77-Do)") (class "Default")
      (node (ref "D77") (pin "1") (pinfunction "Do_1") (pintype "output"))
      (node (ref "D78") (pin "3") (pinfunction "Di_3") (pintype "input"))
    )
    (net (code "103") (name "Net-(D78-Do)") (class "Default")
      (node (ref "D78") (pin "1") (pinfunction "Do_1") (pintype "output"))
      (node (ref "D79") (pin "3") (pinfunction "Di_3") (pintype "input"))
    )
    (net (code "104") (name "Net-(D79-Do)") (class "Default")
      (node (ref "D79") (pin "1") (pinfunction "Do_1") (pintype "output"))
      (node (ref "D80") (pin "3") (pinfunction "Di_3") (pintype "input"))
    )
    (net (code "105") (name "Net-(D80-Do)") (class "Default")
      (node (ref "D80") (pin "1") (pinfunction "Do_1") (pintype "output"))
      (node (ref "D81") (pin "3") (pinfunction "Di_3") (pintype "input"))
    )
    (net (code "106") (name "Net-(D81-Do)") (class "Default")
      (node (ref "D81") (pin "1") (pinfunction "Do_1") (pintype "output"))
      (node (ref "D82") (pin "3") (pinfunction "Di_3") (pintype "input"))
    )
    (net (code "107") (name "Net-(D82-Do)") (class "Default")
      (node (ref "D82") (pin "1") (pinfunction "Do_1") (pintype "output"))
      (node (ref "D83") (pin "3") (pinfunction "Di_3") (pintype "input"))
    )
    (net (code "108") (name "Net-(D83-Do)") (class "Default")
      (node (ref "D83") (pin "1") (pinfunction "Do_1") (pintype "output"))
      (node (ref "D84") (pin "3") (pinfunction "Di_3") (pintype "input"))
    )
    (net (code "109") (name "Net-(D84-Do)") (class "Default")
      (node (ref "D84") (pin "1") (pinfunction "Do_1") (pintype "output"))
      (node (ref "D85") (pin "3") (pinfunction "Di_3") (pintype "input"))
    )
    (net (code "110") (name "Net-(D85-Do)") (class "Default")
      (node (ref "D85") (pin "1") (pinfunction "Do_1") (pintype "output"))
      (node (ref "D86") (pin "3") (pinfunction "Di_3") (pintype "input"))
    )
    (net (code "111") (name "Net-(D86-Do)") (class "Default")
      (node (ref "D86") (pin "1") (pinfunction "Do_1") (pintype "output"))
      (node (ref "D87") (pin "3") (pinfunction "Di_3") (pintype "input"))
    )
    (net (code "112") (name "Net-(D87-Do)") (class "Default")
      (node (ref "D87") (pin "1") (pinfunction "Do_1") (pintype "output"))
      (node (ref "D88") (pin "3") (pinfunction "Di_3") (pintype "input"))
    )
    (net (code "113") (name "Net-(D88-Do)") (class "Default")
      (node (ref "D88") (pin "1") (pinfunction "Do_1") (pintype "output"))
      (node (ref "D89") (pin "3") (pinfunction "Di_3") (pintype "input"))
    )
    (net (code "114") (name "Net-(D89-Do)") (class "Default")
      (node (ref "D89") (pin "1") (pinfunction "Do_1") (pintype "output"))
      (node (ref "D90") (pin "3") (pinfunction "Di_3") (pintype "input"))
    )
    (net (code "115") (name "Net-(D90-Do)") (class "Default")
      (node (ref "D90") (pin "1") (pinfunction "Do_1") (pintype "output"))
      (node (ref "D91") (pin "3") (pinfunction "Di_3") (pintype "input"))
    )
    (net (code "116") (name "Net-(D91-Do)") (class "Default")
      (node (ref "D91") (pin "1") (pinfunction "Do_1") (pintype "output"))
      (node (ref "D92") (pin "3") (pinfunction "Di_3") (pintype "input"))
    )
    (net (code "117") (name "Net-(D92-Do)") (class "Default")
      (node (ref "D92") (pin "1") (pinfunction "Do_1") (pintype "output"))
      (node (ref "D93") (pin "3") (pinfunction "Di_3") (pintype "input"))
    )
    (net (code "118") (name "Net-(D93-Do)") (class "Default")
      (node (ref "D93") (pin "1") (pinfunction "Do_1") (pintype "output"))
      (node (ref "D94") (pin "3") (pinfunction "Di_3") (pintype "input"))
    )
    (net (code "119") (name "Net-(D94-Do)") (class "Default")
      (node (ref "D94") (pin "1") (pinfunction "Do_1") (pintype "output"))
      (node (ref "D95") (pin "3") (pinfunction "Di_3") (pintype "input"))
    )
    (net (code "120") (name "Net-(D95-Do)") (class "Default")
      (node (ref "D95") (pin "1") (pinfunction "Do_1") (pintype "output"))
      (node (ref "D96") (pin "3") (pinfunction "Di_3") (pintype "input"))
    )
    (net (code "121") (name "Net-(D96-Do)") (class "Default")
      (node (ref "D96") (pin "1") (pinfunction "Do_1") (pintype "output"))
      (node (ref "D97") (pin "3") (pinfunction "Di_3") (pintype "input"))
    )
    (net (code "122") (name "Net-(D97-Do)") (class "Default")
      (node (ref "D97") (pin "1") (pinfunction "Do_1") (pintype "output"))
      (node (ref "D98") (pin "3") (pinfunction "Di_3") (pintype "input"))
    )
    (net (code "123") (name "Net-(D98-Do)") (class "Default")
      (node (ref "D98") (pin "1") (pinfunction "Do_1") (pintype "output"))
      (node (ref "D99") (pin "3") (pinfunction "Di_3") (pintype "input"))
    )
    (net (code "124") (name "Net-(D100-Di)") (class "Default")
      (node (ref "D100") (pin "3") (pinfunction "Di_3") (pintype "input"))
      (node (ref "D99") (pin "1") (pinfunction "Do_1") (pintype "output"))
    )
    (net (code "125") (name "Net-(D100-Do)") (class "Default")
      (node (ref "D100") (pin "1") (pinfunction "Do_1") (pintype "output"))
      (node (ref "D101") (pin "3") (pinfunction "Di_3") (pintype "input"))
    )
    (net (code "126") (name "Net-(D101-Do)") (class "Default")
      (node (ref "D101") (pin "1") (pinfunction "Do_1") (pintype "output"))
      (node (ref "D102") (pin "3") (pinfunction "Di_3") (pintype "input"))
    )
    (net (code "127") (name "Net-(D102-Do)") (class "Default")
      (node (ref "D102") (pin "1") (pinfunction "Do_1") (pintype "output"))
      (node (ref "D103") (pin "3") (pinfunction "Di_3") (pintype "input"))
    )
    (net (code "128") (name "Net-(D103-Do)") (class "Default")
      (node (ref "D103") (pin "1") (pinfunction "Do_1") (pintype "output"))
      (node (ref "D104") (pin "3") (pinfunction "Di_3") (pintype "input"))
    )
    (net (code "129") (name "Net-(D104-Do)") (class "Default")
      (node (ref "D104") (pin "1") (pinfunction "Do_1") (pintype "output"))
      (node (ref "D105") (pin "3") (pinfunction "Di_3") (pintype "input"))
    )
    (net (code "130") (name "Net-(D105-Do)") (class "Default")
      (node (ref "D105") (pin "1") (pinfunction "Do_1") (pintype "output"))
      (node (ref "D106") (pin "3") (pinfunction "Di_3") (pintype "input"))
    )
    (net (code "131") (name "Net-(D106-Do)") (class "Default")
      (node (ref "D106") (pin "1") (pinfunction "Do_1") (pintype "output"))
      (node (ref "D107") (pin "3") (pinfunction "Di_3") (pintype "input"))
    )
    (net (code "132") (name "Net-(D107-Do)") (class "Default")
      (node (ref "D107") (pin "1") (pinfunction "Do_1") (pintype "output"))
      (node (ref "D108") (pin "3") (pinfunction "Di_3") (pintype "input"))
    )
    (net (code "133") (name "Net-(D108-Do)") (class "Default")
      (node (ref "D108") (pin "1") (pinfunction "Do_1") (pintype "output"))
      (node (ref "D109") (pin "3") (pinfunction "Di_3") (pintype "input"))
    )
    (net (code "134") (name "Net-(D109-Do)") (class "Default")
      (node (ref "D109") (pin "1") (pinfunction "Do_1") (pintype "output"))
      (node (ref "D110") (pin "3") (pinfunction "Di_3") (pintype "input"))
    )
    (net (code "135") (name "Net-(D110-Do)") (class "Default")
      (node (ref "D110") (pin "1") (pinfunction "Do_1") (pintype "output"))
      (node (ref "D111") (pin "3") (pinfunction "Di_3") (pintype "input"))
    )
    (net (code "136") (name "Net-(D111-Do)") (class "Default")
      (node (ref "D111") (pin "1") (pinfunction "Do_1") (pintype "output"))
      (node (ref "D112") (pin "3") (pinfunction "Di_3") (pintype "input"))
    )
    (net (code "137") (name "Net-(D112-Do)") (class "Default")
      (node (ref "D112") (pin "1") (pinfunction "Do_1") (pintype "output"))
      (node (ref "D113") (pin "3") (pinfunction "Di_3") (pintype "input"))
    )
    (net (code "138") (name "Net-(D113-Do)") (class "Default")
      (node (ref "D113") (pin "1") (pinfunction "Do_1") (pintype "output"))
      (node (ref "D114") (pin "3") (pinfunction "Di_3") (pintype "input"))
    )
    (net (code "139") (name "Net-(D114-Do)") (class "Default")
      (node (ref "D114") (pin "1") (pinfunction "Do_1") (pintype "output"))
      (node (ref "D115") (pin "3") (pinfunction "Di_3") (pintype "input"))
    )
    (net (code "140") (name "Net-(D115-Do)") (class "Default")
      (node (ref "D115") (pin "1") (pinfunction "Do_1") (pintype "output"))
      (node (ref "D116") (pin "3") (pinfunction "Di_3") (pintype "input"))
    )
    (net (code "141") (name "Net-(D116-Do)") (class "Default")
      (node (ref "D116") (pin "1") (pinfunction "Do_1") (pintype "output"))
      (node (ref "D117") (pin "3") (pinfunction "Di_3") (pintype "input"))
    )
    (net (code "142") (name "Net-(D117-Do)") (class "Default")
      (node (ref "D117") (pin "1") (pinfunction "Do_1") (pintype "output"))
      (node (ref "D118") (pin "3") (pinfunction "Di_3") (pintype "input"))
    )
    (net (code "143") (name "Net-(D118-Do)") (class "Default")
      (node (ref "D118") (pin "1") (pinfunction "Do_1") (pintype "output"))
      (node (ref "D119") (pin "3") (pinfunction "Di_3") (pintype "input"))
    )
    (net (code "144") (name "Net-(D119-Do)") (class "Default")
      (node (ref "D119") (pin "1") (pinfunction "Do_1") (pintype "output"))
      (node (ref "D120") (pin "3") (pinfunction "Di_3") (pintype "input"))
    )
    (net (code "145") (name "Net-(D120-Do)") (class "Default")
      (node (ref "D120") (pin "1") (pinfunction "Do_1") (pintype "output"))
      (node (ref "D121") (pin "3") (pinfunction "Di_3") (pintype "input"))
    )
    (net (code "146") (name "Net-(D121-Do)") (class "Default")
      (node (ref "D121") (pin "1") (pinfunction "Do_1") (pintype "output"))
      (node (ref "D122") (pin "3") (pinfunction "Di_3") (pintype "input"))
    )
    (net (code "147") (name "Net-(D122-Do)") (class "Default")
      (node (ref "D122") (pin "1") (pinfunction "Do_1") (pintype "output"))
      (node (ref "D123") (pin "3") (pinfunction "Di_3") (pintype "input"))
    )
    (net (code "148") (name "Net-(D123-Do)") (class "Default")
      (node (ref "D123") (pin "1") (pinfunction "Do_1") (pintype "output"))
      (node (ref "D124") (pin "3") (pinfunction "Di_3") (pintype "input"))
    )
    (net (code "149") (name "Net-(D124-Do)") (class "Default")
      (node (ref "D124") (pin "1") (pinfunction "Do_1") (pintype "output"))
      (node (ref "D125") (pin "3") (pinfunction "Di_3") (pintype "input"))
    )
    (net (code "150") (name "Net-(D125-Do)") (class "Default")
      (node (ref "D125") (pin "1") (pinfunction "Do_1") (pintype "output"))
      (node (ref "D126") (pin "3") (pinfunction "Di_3") (pintype "input"))
    )
    (net (code "151") (name "Net-(D126-Do)") (class "Default")
      (node (ref "D126") (pin "1") (pinfunction "Do_1") (pintype "output"))
      (node (ref "D127") (pin "3") (pinfunction "Di_3") (pintype "input"))
    )
    (net (code "152") (name "Net-(D127-Do)") (class "Default")
      (node (ref "D127") (pin "1") (pinfunction "Do_1") (pintype "output"))
      (node (ref "D128") (pin "3") (pinfunction "Di_3") (pintype "input"))
    )
    (net (code "153") (name "Net-(R1-Pad2)") (class "Default")
      (node (ref "R1") (pin "2") (pinfunction "2_2") (pintype "passive"))
      (node (ref "SW1") (pin "1") (pinfunction "1_1") (pintype "passive"))
    )
    (net (code "154") (name "VUSB") (class "Default")
      (node (ref "C1") (pin "1") (pinfunction "1_1") (pintype "passive"))
      (node (ref "C10") (pin "1") (pinfunction "1_1") (pintype "passive"))
      (node (ref "C11") (pin "1") (pinfunction "1_1") (pintype "passive"))
      (node (ref "C12") (pin "1") (pinfunction "1_1") (pintype "passive"))
      (node (ref "C13") (pin "1") (pinfunction "1_1") (pintype "passive"))
      (node (ref "C14") (pin "1") (pinfunction "1_1") (pintype "passive"))
      (node (ref "C15") (pin "1") (pinfunction "1_1") (pintype "passive"))
      (node (ref "C16") (pin "1") (pinfunction "1_1") (pintype "passive"))
      (node (ref "C17") (pin "1") (pinfunction "1_1") (pintype "passive"))
      (node (ref "C18") (pin "1") (pinfunction "1_1") (pintype "passive"))
      (node (ref "C19") (pin "1") (pinfunction "1_1") (pintype "passive"))
      (node (ref "C2") (pin "1") (pinfunction "1_1") (pintype "passive"))
      (node (ref "C20") (pin "1") (pinfunction "1_1") (pintype "passive"))
      (node (ref "C21") (pin "1") (pinfunction "1_1") (pintype "passive"))
      (node (ref "C22") (pin "1") (pinfunction "1_1") (pintype "passive"))
      (node (ref "C23") (pin "1") (pinfunction "1_1") (pintype "passive"))
      (node (ref "C24") (pin "1") (pinfunction "1_1") (pintype "passive"))
      (node (ref "C25") (pin "1") (pinfunction "1_1") (pintype "passive"))
      (node (ref "C26") (pin "1") (pinfunction "1_1") (pintype "passive"))
      (node (ref "C27") (pin "1") (pinfunction "1_1") (pintype "passive"))
      (node (ref "C28") (pin "1") (pinfunction "1_1") (pintype "passive"))
      (node (ref "C29") (pin "1") (pinfunction "1_1") (pintype "passive"))
      (node (ref "C3") (pin "1") (pinfunction "1_1") (pintype "passive"))
      (node (ref "C30") (pin "1") (pinfunction "1_1") (pintype "passive"))
      (node (ref "C31") (pin "1") (pinfunction "1_1") (pintype "passive"))
      (node (ref "C32") (pin "1") (pinfunction "1_1") (pintype "passive"))
      (node (ref "C33") (pin "1") (pinfunction "1_1") (pintype "passive"))
      (node (ref "C34") (pin "1") (pinfunction "1_1") (pintype "passive"))
      (node (ref "C35") (pin "1") (pinfunction "1_1") (pintype "passive"))
      (node (ref "C36") (pin "1") (pinfunction "1_1") (pintype "passive"))
      (node (ref "C37") (pin "1") (pinfunction "1_1") (pintype "passive"))
      (node (ref "C38") (pin "1") (pinfunction "1_1") (pintype "passive"))
      (node (ref "C39") (pin "1") (pinfunction "1_1") (pintype "passive"))
      (node (ref "C4") (pin "1") (pinfunction "1_1") (pintype "passive"))
      (node (ref "C40") (pin "1") (pinfunction "1_1") (pintype "passive"))
      (node (ref "C41") (pin "1") (pinfunction "1_1") (pintype "passive"))
      (node (ref "C42") (pin "1") (pinfunction "1_1") (pintype "passive"))
      (node (ref "C43") (pin "1") (pinfunction "1_1") (pintype "passive"))
      (node (ref "C44") (pin "1") (pinfunction "1_1") (pintype "passive"))
      (node (ref "C45") (pin "1") (pinfunction "1_1") (pintype "passive"))
      (node (ref "C46") (pin "1") (pinfunction "1_1") (pintype "passive"))
      (node (ref "C47") (pin "1") (pinfunction "1_1") (pintype "passive"))
      (node (ref "C48") (pin "1") (pinfunction "1_1") (pintype "passive"))
      (node (ref "C49") (pin "1") (pinfunction "1_1") (pintype "passive"))
      (node (ref "C5") (pin "1") (pinfunction "1_1") (pintype "passive"))
      (node (ref "C50") (pin "1") (pinfunction "1_1") (pintype "passive"))
      (node (ref "C51") (pin "1") (pinfunction "1_1") (pintype "passive"))
      (node (ref "C52") (pin "1") (pinfunction "1_1") (pintype "passive"))
      (node (ref "C53") (pin "1") (pinfunction "1_1") (pintype "passive"))
      (node (ref "C54") (pin "1") (pinfunction "1_1") (pintype "passive"))
      (node (ref "C55") (pin "1") (pinfunction "1_1") (pintype "passive"))
      (node (ref "C56") (pin "1") (pinfunction "1_1") (pintype "passive"))
      (node (ref "C57") (pin "1") (pinfunction "1_1") (pintype "passive"))
      (node (ref "C58") (pin "1") (pinfunction "1_1") (pintype "passive"))
      (node (ref "C59") (pin "1") (pinfunction "1_1") (pintype "passive"))
      (node (ref "C6") (pin "1") (pinfunction "1_1") (pintype "passive"))
      (node (ref "C60") (pin "1") (pinfunction "1_1") (pintype "passive"))
      (node (ref "C61") (pin "1") (pinfunction "1_1") (pintype "passive"))
      (node (ref "C62") (pin "1") (pinfunction "1_1") (pintype "passive"))
      (node (ref "C63") (pin "1") (pinfunction "1_1") (pintype "passive"))
      (node (ref "C64") (pin "1") (pinfunction "1_1") (pintype "passive"))
      (node (ref "C65") (pin "1") (pinfunction "1_1") (pintype "passive"))
      (node (ref "C66") (pin "1") (pinfunction "1_1") (pintype "passive"))
      (node (ref "C7") (pin "1") (pinfunction "1_1") (pintype "passive"))
      (node (ref "C8") (pin "1") (pinfunction "1_1") (pintype "passive"))
      (node (ref "C9") (pin "1") (pinfunction "1_1") (pintype "passive"))
      (node (ref "D1") (pin "4") (pinfunction "V+_4") (pintype "power_in"))
      (node (ref "D100") (pin "4") (pinfunction "V+_4") (pintype "power_in"))
      (node (ref "D101") (pin "4") (pinfunction "V+_4") (pintype "power_in"))
      (node (ref "D102") (pin "4") (pinfunction "V+_4") (pintype "power_in"))
      (node (ref "D103") (pin "4") (pinfunction "V+_4") (pintype "power_in"))
      (node (ref "D104") (pin "4") (pinfunction "V+_4") (pintype "power_in"))
      (node (ref "D105") (pin "4") (pinfunction "V+_4") (pintype "power_in"))
      (node (ref "D106") (pin "4") (pinfunction "V+_4") (pintype "power_in"))
      (node (ref "D107") (pin "4") (pinfunction "V+_4") (pintype "power_in"))
      (node (ref "D108") (pin "4") (pinfunction "V+_4") (pintype "power_in"))
      (node (ref "D109") (pin "4") (pinfunction "V+_4") (pintype "power_in"))
      (node (ref "D110") (pin "4") (pinfunction "V+_4") (pintype "power_in"))
      (node (ref "D111") (pin "4") (pinfunction "V+_4") (pintype "power_in"))
      (node (ref "D112") (pin "4") (pinfunction "V+_4") (pintype "power_in"))
      (node (ref "D113") (pin "4") (pinfunction "V+_4") (pintype "power_in"))
      (node (ref "D114") (pin "4") (pinfunction "V+_4") (pintype "power_in"))
      (node (ref "D115") (pin "4") (pinfunction "V+_4") (pintype "power_in"))
      (node (ref "D116") (pin "4") (pinfunction "V+_4") (pintype "power_in"))
      (node (ref "D117") (pin "4") (pinfunction "V+_4") (pintype "power_in"))
      (node (ref "D118") (pin "4") (pinfunction "V+_4") (pintype "power_in"))
      (node (ref "D119") (pin "4") (pinfunction "V+_4") (pintype "power_in"))
      (node (ref "D120") (pin "4") (pinfunction "V+_4") (pintype "power_in"))
      (node (ref "D121") (pin "4") (pinfunction "V+_4") (pintype "power_in"))
      (node (ref "D122") (pin "4") (pinfunction "V+_4") (pintype "power_in"))
      (node (ref "D123") (pin "4") (pinfunction "V+_4") (pintype "power_in"))
      (node (ref "D124") (pin "4") (pinfunction "V+_4") (pintype "power_in"))
      (node (ref "D125") (pin "4") (pinfunction "V+_4") (pintype "power_in"))
      (node (ref "D126") (pin "4") (pinfunction "V+_4") (pintype "power_in"))
      (node (ref "D127") (pin "4") (pinfunction "V+_4") (pintype "power_in"))
      (node (ref "D128") (pin "4") (pinfunction "V+_4") (pintype "power_in"))
      (node (ref "D2") (pin "4") (pinfunction "V+_4") (pintype "power_in"))
      (node (ref "D3") (pin "4") (pinfunction "V+_4") (pintype "power_in"))
      (node (ref "D4") (pin "4") (pinfunction "V+_4") (pintype "power_in"))
      (node (ref "D69") (pin "4") (pinfunction "V+_4") (pintype "power_in"))
      (node (ref "D70") (pin "4") (pinfunction "V+_4") (pintype "power_in"))
      (node (ref "D71") (pin "4") (pinfunction "V+_4") (pintype "power_in"))
      (node (ref "D72") (pin "4") (pinfunction "V+_4") (pintype "power_in"))
      (node (ref "D73") (pin "4") (pinfunction "V+_4") (pintype "power_in"))
      (node (ref "D74") (pin "4") (pinfunction "V+_4") (pintype "power_in"))
      (node (ref "D75") (pin "4") (pinfunction "V+_4") (pintype "power_in"))
      (node (ref "D76") (pin "4") (pinfunction "V+_4") (pintype "power_in"))
      (node (ref "D77") (pin "4") (pinfunction "V+_4") (pintype "power_in"))
      (node (ref "D78") (pin "4") (pinfunction "V+_4") (pintype "power_in"))
      (node (ref "D79") (pin "4") (pinfunction "V+_4") (pintype "power_in"))
      (node (ref "D80") (pin "4") (pinfunction "V+_4") (pintype "power_in"))
      (node (ref "D81") (pin "4") (pinfunction "V+_4") (pintype "power_in"))
      (node (ref "D82") (pin "4") (pinfunction "V+_4") (pintype "power_in"))
      (node (ref "D83") (pin "4") (pinfunction "V+_4") (pintype "power_in"))
      (node (ref "D84") (pin "4") (pinfunction "V+_4") (pintype "power_in"))
      (node (ref "D85") (pin "4") (pinfunction "V+_4") (pintype "power_in"))
      (node (ref "D86") (pin "4") (pinfunction "V+_4") (pintype "power_in"))
      (node (ref "D87") (pin "4") (pinfunction "V+_4") (pintype "power_in"))
      (node (ref "D88") (pin "4") (pinfunction "V+_4") (pintype "power_in"))
      (node (ref "D89") (pin "4") (pinfunction "V+_4") (pintype "power_in"))
      (node (ref "D90") (pin "4") (pinfunction "V+_4") (pintype "power_in"))
      (node (ref "D91") (pin "4") (pinfunction "V+_4") (pintype "power_in"))
      (node (ref "D92") (pin "4") (pinfunction "V+_4") (pintype "power_in"))
      (node (ref "D93") (pin "4") (pinfunction "V+_4") (pintype "power_in"))
      (node (ref "D94") (pin "4") (pinfunction "V+_4") (pintype "power_in"))
      (node (ref "D95") (pin "4") (pinfunction "V+_4") (pintype "power_in"))
      (node (ref "D96") (pin "4") (pinfunction "V+_4") (pintype "power_in"))
      (node (ref "D97") (pin "4") (pinfunction "V+_4") (pintype "power_in"))
      (node (ref "D98") (pin "4") (pinfunction "V+_4") (pintype "power_in"))
      (node (ref "D99") (pin "4") (pinfunction "V+_4") (pintype "power_in"))
      (node (ref "J1") (pin "A4") (pinfunction "VBUS_A4") (pintype "passive"))
      (node (ref "J1") (pin "A9") (pinfunction "VBUS_A9") (pintype "passive"))
      (node (ref "J1") (pin "B4") (pinfunction "VBUS_B4") (pintype "passive"))
      (node (ref "J1") (pin "B9") (pinfunction "VBUS_B9") (pintype "passive"))
      (node (ref "P2") (pin "2") (pinfunction "2_2") (pintype "passive"))
      (node (ref "R1") (pin "1") (pinfunction "1_1") (pintype "passive"))
      (node (ref "U1") (pin "2") (pinfunction "VDD_2") (pintype "power_in"))
    )
    (net (code "155") (name "unconnected-(J1-SBU1-PadA8)") (class "Default")
      (node (ref "J1") (pin "A8") (pinfunction "SBU1_A8") (pintype "passive+no_connect"))
    )
    (net (code "156") (name "unconnected-(J1-SBU2-PadB8)") (class "Default")
      (node (ref "J1") (pin "B8") (pinfunction "SBU2_B8") (pintype "passive+no_connect"))
    )
    (net (code "157") (name "unconnected-(U1-PA6{slash}MISO-Pad11)") (class "Default")
      (node (ref "U1") (pin "11") (pinfunction "PA6/MISO_11") (pintype "bidirectional"))
    )
    (net (code "158") (name "unconnected-(U1-PB0-Pad13)") (class "Default")
      (node (ref "U1") (pin "13") (pinfunction "PB0_13") (pintype "bidirectional"))
    )
    (net (code "159") (name "unconnected-(U1-PB3-Pad14)") (class "Default")
      (node (ref "U1") (pin "14") (pinfunction "PB3_14") (pintype "bidirectional"))
    )
    (net (code "160") (name "unconnected-(U1-PB4-Pad15)") (class "Default")
      (node (ref "U1") (pin "15") (pinfunction "PB4_15") (pintype "bidirectional"))
    )
    (net (code "161") (name "unconnected-(U1-PC14{slash}CC1-Pad28)") (class "Default")
      (node (ref "U1") (pin "28") (pinfunction "PC14/CC1_28") (pintype "bidirectional"))
    )
    (net (code "162") (name "unconnected-(U1-PC15{slash}CC2-Pad1)") (class "Default")
      (node (ref "U1") (pin "1") (pinfunction "PC15/CC2_1") (pintype "bidirectional"))
    )
  )
)
